# design.net
KiCad netlist of a schematic drawn in Altium Designer
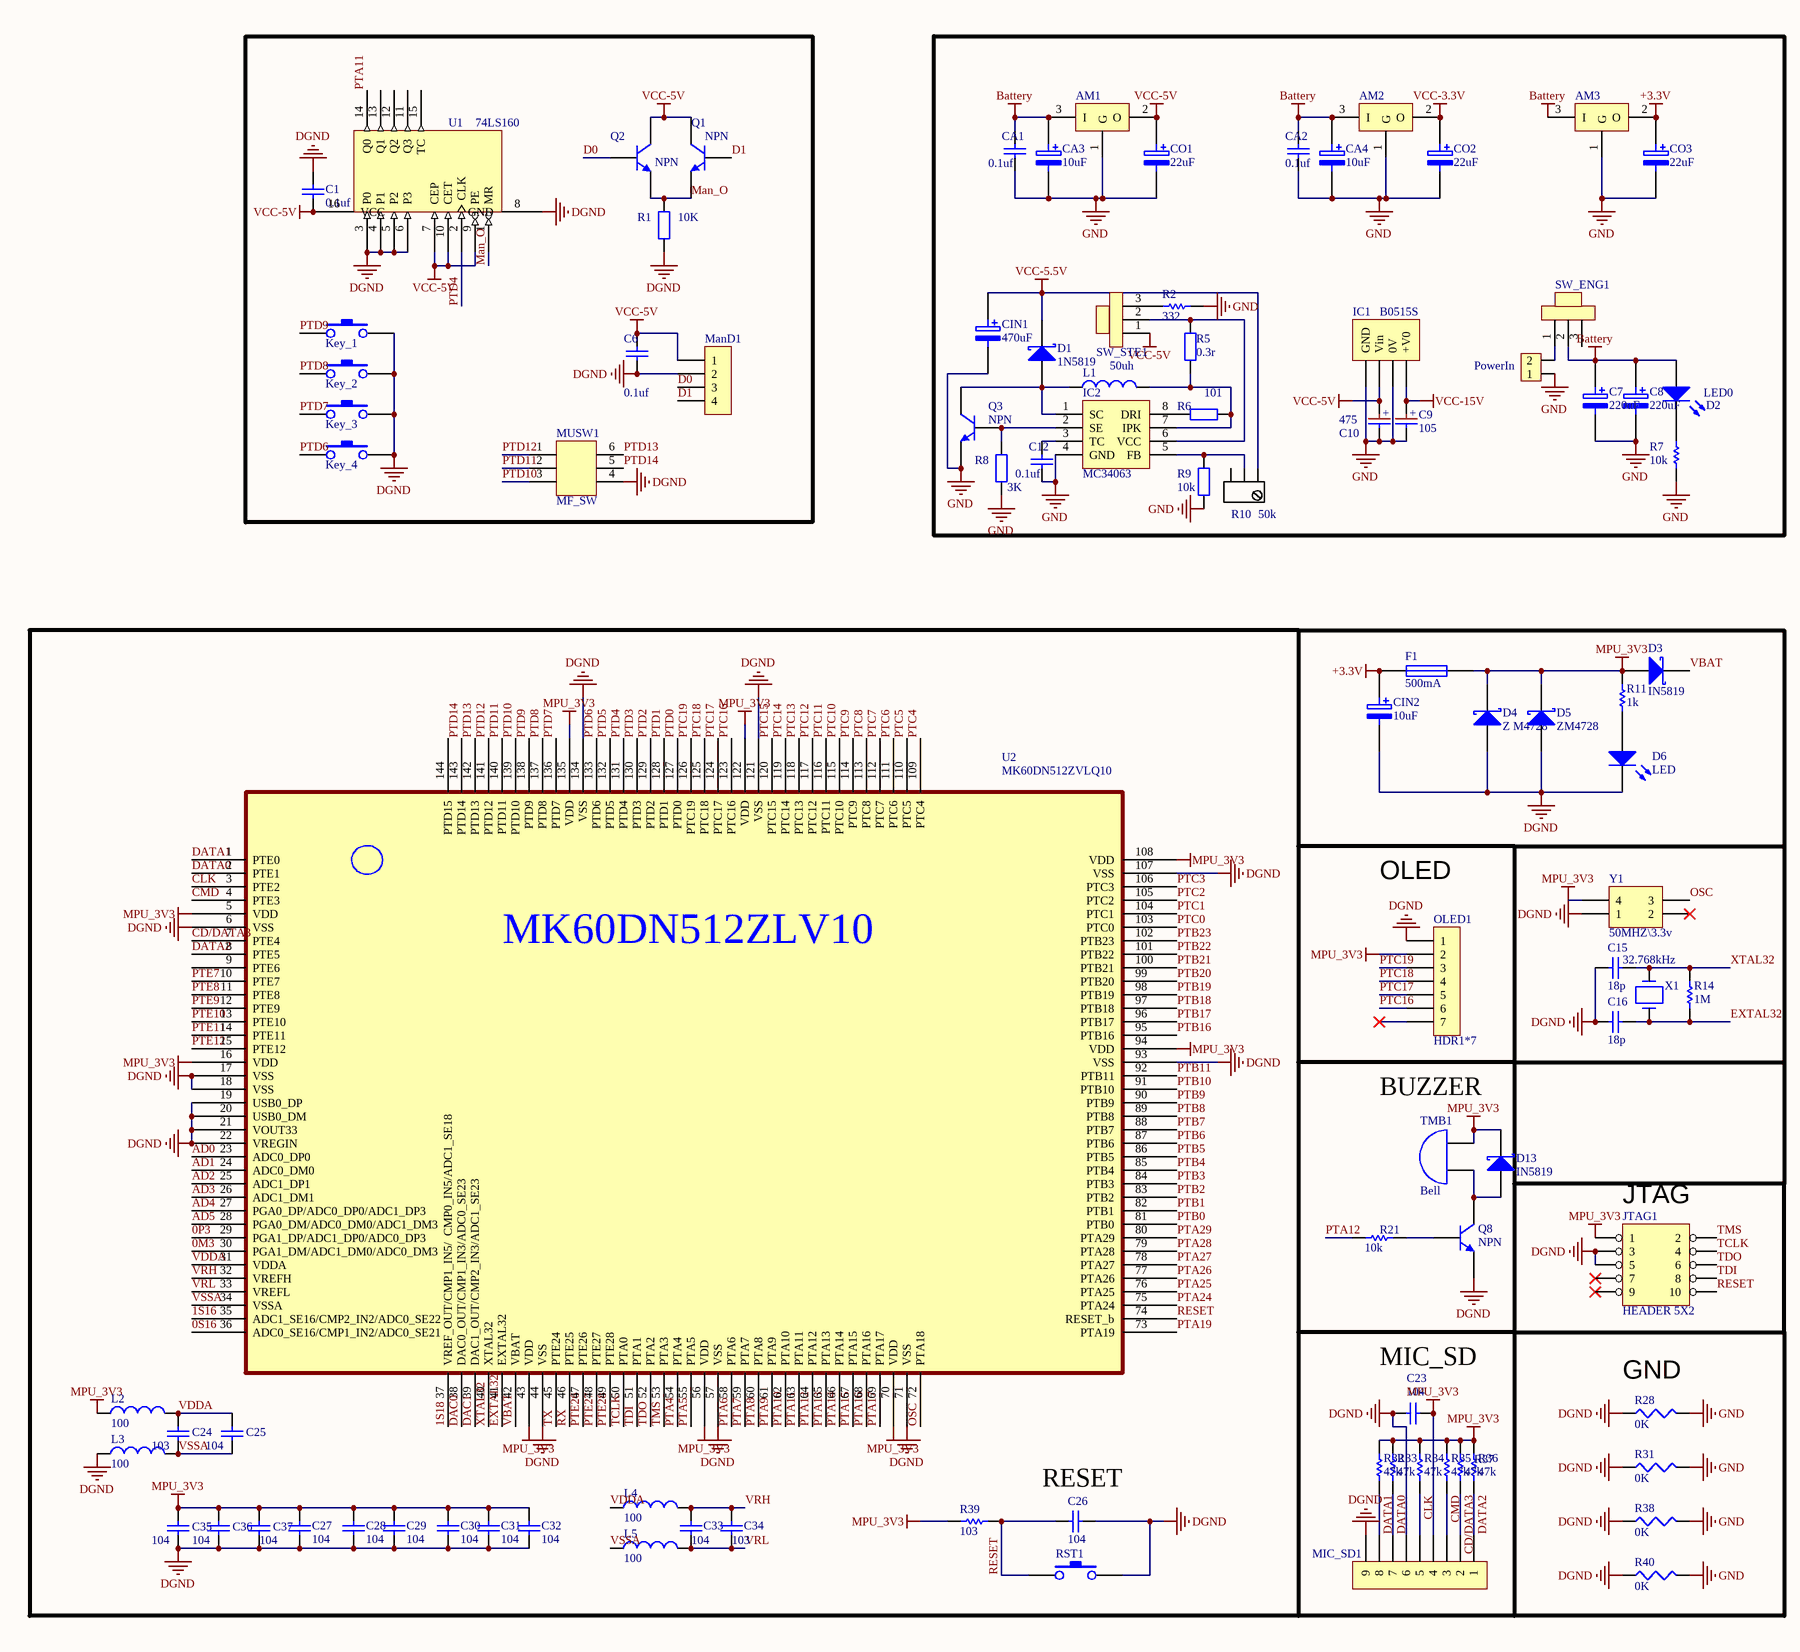
[diagram p0: 夏友.SchDoc, left]
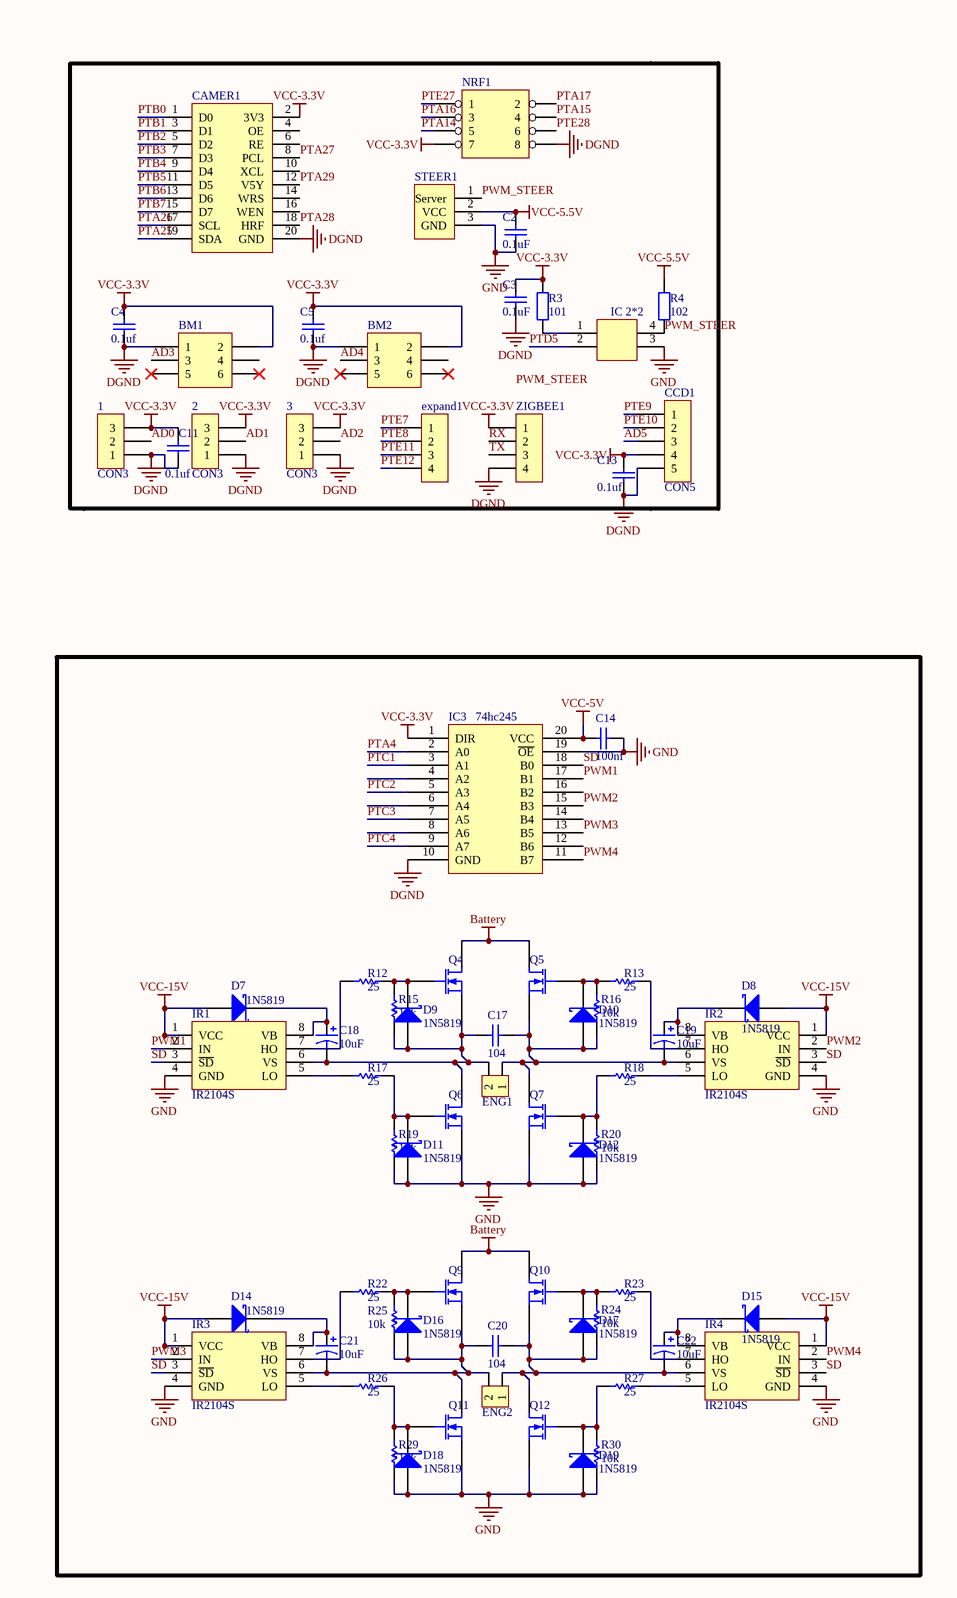
[diagram p1: 夏友.SchDoc, right]

(export (version "E")
  (design (tool "Eeschema 10.0.6"))
  (components
    (comp (ref "*1") (value "IC 2*2") (footprint "PC817") (libsource (lib "component") (part "IC 2*2")))
    (comp (ref "1")
      (value "CON3")
      (footprint "HDR1*3")
      (description "Connector")
      (libsource (lib "Miscellaneous Devices") (part "CON3"))
    )
    (comp (ref "2")
      (value "CON3")
      (footprint "HDR1*3")
      (description "Connector")
      (libsource (lib "Miscellaneous Devices") (part "CON3"))
    )
    (comp (ref "3")
      (value "CON3")
      (footprint "HDR1*3")
      (description "Connector")
      (libsource (lib "Miscellaneous Devices") (part "CON3"))
    )
    (comp (ref "AM1") (value "AMS1117") (footprint "SOT223") (libsource (lib "component") (part "AMS1117")))
    (comp (ref "AM2") (value "AMS1117") (footprint "SOT223") (libsource (lib "component") (part "AMS1117")))
    (comp (ref "AM3") (value "AMS1117") (footprint "SOT223") (libsource (lib "component") (part "AMS1117")))
    (comp (ref "BM1")
      (value "编码器左")
      (footprint "HDR2*3")
      (description "Header, 3-Pin, Dual row")
      (fields (field (name "PUBLISHER") "Altium Limited"))
      (libsource (lib "Miscellaneous Connectors") (part "Header 3X2"))
    )
    (comp (ref "BM2")
      (value "编码器左")
      (footprint "HDR2*3")
      (description "Header, 3-Pin, Dual row")
      (fields (field (name "PUBLISHER") "Altium Limited"))
      (libsource (lib "Miscellaneous Connectors") (part "Header 3X2"))
    )
    (comp (ref "C1")
      (value "0.1uf")
      (footprint "0603")
      (description "Capacitor (Semiconductor SIM Model)")
      (fields (field (name "Comment") "Cap Semi") (field (name "PUBLISHER") "Altium Limited"))
      (libsource (lib "Smartcar_Sheet") (part "Cap Semi_1"))
    )
    (comp (ref "C2")
      (value "0.1uF")
      (footprint "0603")
      (description "Capacitor")
      (fields (field (name "Comment") "Cap") (field (name "PUBLISHER") "Altium Limited"))
      (libsource (lib "省赛") (part "Cap"))
    )
    (comp (ref "C3")
      (value "0.1uF")
      (footprint "0603")
      (description "Capacitor")
      (fields (field (name "Comment") "Cap") (field (name "PUBLISHER") "Altium Limited"))
      (libsource (lib "省赛") (part "Cap"))
    )
    (comp (ref "C4")
      (value "0.1uf")
      (footprint "0603")
      (description "Capacitor (Semiconductor SIM Model)")
      (fields (field (name "Comment") "Cap Semi") (field (name "PUBLISHER") "Altium Limited"))
      (libsource (lib "Smartcar_Sheet") (part "Cap Semi_1"))
    )
    (comp (ref "C5")
      (value "0.1uf")
      (footprint "0603")
      (description "Capacitor (Semiconductor SIM Model)")
      (fields (field (name "Comment") "Cap Semi") (field (name "PUBLISHER") "Altium Limited"))
      (libsource (lib "Smartcar_Sheet") (part "Cap Semi_1"))
    )
    (comp (ref "C6")
      (value "0.1uf")
      (footprint "0603")
      (description "Capacitor (Semiconductor SIM Model)")
      (fields (field (name "Comment") "Cap Semi") (field (name "PUBLISHER") "Altium Limited"))
      (libsource (lib "Smartcar_Sheet") (part "Cap Semi_1"))
    )
    (comp (ref "C7")
      (value "220uF")
      (footprint "CAPMP7344X43N")
      (description "Electrolytic Capacitor")
      (libsource (lib "FS44B0") (part "ELECTRO2"))
    )
    (comp (ref "C8")
      (value "220uF")
      (footprint "CAPMP7344X43N")
      (description "Electrolytic Capacitor")
      (libsource (lib "FS44B0") (part "ELECTRO2"))
    )
    (comp (ref "C9")
      (value "105")
      (footprint "0805")
      (description "电容器")
      (libsource (lib "Smartcar_Sheet") (part "Cap--0805"))
    )
    (comp (ref "C10")
      (value "475")
      (footprint "0805")
      (description "电容器")
      (libsource (lib "Smartcar_Sheet") (part "Cap--0805"))
    )
    (comp (ref "C11")
      (value "0.1uf")
      (footprint "0603")
      (description "Capacitor (Semiconductor SIM Model)")
      (fields (field (name "Comment") "Cap Semi") (field (name "PUBLISHER") "Altium Limited"))
      (libsource (lib "Smartcar_Sheet") (part "Cap Semi_1"))
    )
    (comp (ref "C12")
      (value "0.1uf")
      (footprint "0603")
      (description "Capacitor (Semiconductor SIM Model)")
      (fields (field (name "Comment") "Cap Semi") (field (name "PUBLISHER") "Altium Limited"))
      (libsource (lib "Smartcar_Sheet") (part "Cap Semi_1"))
    )
    (comp (ref "C13")
      (value "0.1uf")
      (footprint "0603")
      (description "Capacitor (Semiconductor SIM Model)")
      (fields (field (name "Comment") "Cap Semi") (field (name "PUBLISHER") "Altium Limited"))
      (libsource (lib "Smartcar_Sheet") (part "Cap Semi_1"))
    )
    (comp (ref "C14")
      (value "100nf")
      (footprint "0603")
      (description "Capacitor (Semiconductor SIM Model)")
      (fields (field (name "Comment") "Cap Semi") (field (name "PUBLISHER") "Altium Limited"))
      (libsource (lib "Smartcar_Sheet") (part "Cap Semi_1"))
    )
    (comp (ref "C15")
      (value "18p")
      (footprint "0603")
      (description "Capacitor (Semiconductor SIM Model)")
      (fields (field (name "Comment") "Cap Semi") (field (name "PUBLISHER") "Altium Limited"))
      (libsource (lib "Smartcar_Sheet") (part "Cap Semi_1"))
    )
    (comp (ref "C16")
      (value "18p")
      (footprint "0603")
      (description "Capacitor (Semiconductor SIM Model)")
      (fields (field (name "Comment") "Cap Semi") (field (name "PUBLISHER") "Altium Limited"))
      (libsource (lib "Smartcar_Sheet") (part "Cap Semi_1"))
    )
    (comp (ref "C17")
      (value "104")
      (footprint "0603")
      (description "Capacitor (Semiconductor SIM Model)")
      (fields (field (name "Comment") "Cap Semi") (field (name "PUBLISHER") "Altium Limited"))
      (libsource (lib "Smartcar_Sheet") (part "Cap Semi_1"))
    )
    (comp (ref "C18")
      (value "10uF")
      (footprint "C1206")
      (description "Polarized Capacitor (Radial)")
      (fields (field (name "Comment") "1uF") (field (name "PUBLISHER") "Altium Limited"))
      (libsource (lib "Miscellaneous Devices") (part "Cap Pol1"))
    )
    (comp (ref "C19")
      (value "10uF")
      (footprint "C1206")
      (description "Polarized Capacitor (Radial)")
      (fields (field (name "Comment") "1uF") (field (name "PUBLISHER") "Altium Limited"))
      (libsource (lib "Miscellaneous Devices") (part "Cap Pol1"))
    )
    (comp (ref "C20")
      (value "104")
      (footprint "0603")
      (description "Capacitor (Semiconductor SIM Model)")
      (fields (field (name "Comment") "Cap Semi") (field (name "PUBLISHER") "Altium Limited"))
      (libsource (lib "Smartcar_Sheet") (part "Cap Semi_1"))
    )
    (comp (ref "C21")
      (value "10uF")
      (footprint "C1206")
      (description "Polarized Capacitor (Radial)")
      (fields (field (name "Comment") "1uF") (field (name "PUBLISHER") "Altium Limited"))
      (libsource (lib "Miscellaneous Devices") (part "Cap Pol1"))
    )
    (comp (ref "C22")
      (value "10uF")
      (footprint "C1206")
      (description "Polarized Capacitor (Radial)")
      (fields (field (name "Comment") "1uF") (field (name "PUBLISHER") "Altium Limited"))
      (libsource (lib "Miscellaneous Devices") (part "Cap Pol1"))
    )
    (comp (ref "C23")
      (value "104")
      (footprint "0603")
      (description "Capacitor (Semiconductor SIM Model)")
      (fields (field (name "Comment") "Cap Semi") (field (name "PUBLISHER") "Altium Limited"))
      (libsource (lib "Smartcar_Sheet") (part "Cap Semi_1"))
    )
    (comp (ref "C24")
      (value "103")
      (footprint "0603")
      (description "Capacitor (Semiconductor SIM Model)")
      (fields (field (name "Comment") "Cap Semi") (field (name "PUBLISHER") "Altium Limited"))
      (libsource (lib "Smartcar_Sheet") (part "Cap Semi_1"))
    )
    (comp (ref "C25")
      (value "104")
      (footprint "0603")
      (description "Capacitor (Semiconductor SIM Model)")
      (fields (field (name "Comment") "Cap Semi") (field (name "PUBLISHER") "Altium Limited"))
      (libsource (lib "Smartcar_Sheet") (part "Cap Semi_1"))
    )
    (comp (ref "C26")
      (value "104")
      (footprint "0603")
      (description "Capacitor (Semiconductor SIM Model)")
      (fields (field (name "Comment") "Cap Semi") (field (name "PUBLISHER") "Altium Limited"))
      (libsource (lib "Smartcar_Sheet") (part "Cap Semi_1"))
    )
    (comp (ref "C27")
      (value "104")
      (footprint "0603")
      (description "Capacitor (Semiconductor SIM Model)")
      (fields (field (name "Comment") "Cap Semi") (field (name "PUBLISHER") "Altium Limited"))
      (libsource (lib "Smartcar_Sheet") (part "Cap Semi_1"))
    )
    (comp (ref "C28")
      (value "104")
      (footprint "0603")
      (description "Capacitor (Semiconductor SIM Model)")
      (fields (field (name "Comment") "Cap Semi") (field (name "PUBLISHER") "Altium Limited"))
      (libsource (lib "Smartcar_Sheet") (part "Cap Semi_1"))
    )
    (comp (ref "C29")
      (value "104")
      (footprint "0603")
      (description "Capacitor (Semiconductor SIM Model)")
      (fields (field (name "Comment") "Cap Semi") (field (name "PUBLISHER") "Altium Limited"))
      (libsource (lib "Smartcar_Sheet") (part "Cap Semi_1"))
    )
    (comp (ref "C30")
      (value "104")
      (footprint "0603")
      (description "Capacitor (Semiconductor SIM Model)")
      (fields (field (name "Comment") "Cap Semi") (field (name "PUBLISHER") "Altium Limited"))
      (libsource (lib "Smartcar_Sheet") (part "Cap Semi_1"))
    )
    (comp (ref "C31")
      (value "104")
      (footprint "0603")
      (description "Capacitor (Semiconductor SIM Model)")
      (fields (field (name "Comment") "Cap Semi") (field (name "PUBLISHER") "Altium Limited"))
      (libsource (lib "Smartcar_Sheet") (part "Cap Semi_1"))
    )
    (comp (ref "C32")
      (value "104")
      (footprint "0603")
      (description "Capacitor (Semiconductor SIM Model)")
      (fields (field (name "Comment") "Cap Semi") (field (name "PUBLISHER") "Altium Limited"))
      (libsource (lib "Smartcar_Sheet") (part "Cap Semi_1"))
    )
    (comp (ref "C33")
      (value "104")
      (footprint "0603")
      (description "Capacitor (Semiconductor SIM Model)")
      (fields (field (name "Comment") "Cap Semi") (field (name "PUBLISHER") "Altium Limited"))
      (libsource (lib "Smartcar_Sheet") (part "Cap Semi_1"))
    )
    (comp (ref "C34")
      (value "103")
      (footprint "0603")
      (description "Capacitor (Semiconductor SIM Model)")
      (fields (field (name "Comment") "Cap Semi") (field (name "PUBLISHER") "Altium Limited"))
      (libsource (lib "Smartcar_Sheet") (part "Cap Semi_1"))
    )
    (comp (ref "C35")
      (value "104")
      (footprint "0603")
      (description "Capacitor (Semiconductor SIM Model)")
      (fields (field (name "Comment") "Cap Semi") (field (name "PUBLISHER") "Altium Limited"))
      (libsource (lib "Smartcar_Sheet") (part "Cap Semi_1"))
    )
    (comp (ref "C36")
      (value "104")
      (footprint "0603")
      (description "Capacitor (Semiconductor SIM Model)")
      (fields (field (name "Comment") "Cap Semi") (field (name "PUBLISHER") "Altium Limited"))
      (libsource (lib "Smartcar_Sheet") (part "Cap Semi_1"))
    )
    (comp (ref "C37")
      (value "104")
      (footprint "0603")
      (description "Capacitor (Semiconductor SIM Model)")
      (fields (field (name "Comment") "Cap Semi") (field (name "PUBLISHER") "Altium Limited"))
      (libsource (lib "Smartcar_Sheet") (part "Cap Semi_1"))
    )
    (comp (ref "CA1")
      (value "0.1uf")
      (footprint "0603")
      (description "Capacitor (Semiconductor SIM Model)")
      (fields (field (name "Comment") "Cap Semi") (field (name "PUBLISHER") "Altium Limited"))
      (libsource (lib "Smartcar_Sheet") (part "Cap Semi_1"))
    )
    (comp (ref "CA2")
      (value "0.1uf")
      (footprint "0603")
      (description "Capacitor (Semiconductor SIM Model)")
      (fields (field (name "Comment") "Cap Semi") (field (name "PUBLISHER") "Altium Limited"))
      (libsource (lib "Smartcar_Sheet") (part "Cap Semi_1"))
    )
    (comp (ref "CA3")
      (value "10uF")
      (footprint "C1206")
      (description "Electrolytic Capacitor")
      (libsource (lib "FS44B0") (part "ELECTRO2"))
    )
    (comp (ref "CA4")
      (value "10uF")
      (footprint "C1206")
      (description "Electrolytic Capacitor")
      (libsource (lib "FS44B0") (part "ELECTRO2"))
    )
    (comp (ref "CAMER1")
      (value "CAMER")
      (footprint "HDR2*10-10*25")
      (libsource (lib "component") (part "CAMER"))
    )
    (comp (ref "CCD1")
      (value "CON5")
      (footprint "HDR1*5")
      (description "Connector")
      (libsource (lib "Miscellaneous Devices") (part "CON5"))
    )
    (comp (ref "CIN1")
      (value "470uF")
      (footprint "470uf-column")
      (description "Electrolytic Capacitor")
      (libsource (lib "FS44B0") (part "ELECTRO2"))
    )
    (comp (ref "CIN2")
      (value "10uF")
      (footprint "C1206")
      (description "Electrolytic Capacitor")
      (libsource (lib "FS44B0") (part "ELECTRO2"))
    )
    (comp (ref "CO1")
      (value "22uF")
      (footprint "C1206")
      (description "Electrolytic Capacitor")
      (libsource (lib "FS44B0") (part "ELECTRO2"))
    )
    (comp (ref "CO2")
      (value "22uF")
      (footprint "C1206")
      (description "Electrolytic Capacitor")
      (libsource (lib "FS44B0") (part "ELECTRO2"))
    )
    (comp (ref "CO3")
      (value "22uF")
      (footprint "C1206")
      (description "Electrolytic Capacitor")
      (libsource (lib "FS44B0") (part "ELECTRO2"))
    )
    (comp (ref "CON1")
      (value "PowerIn")
      (footprint "Battery")
      (description "Header, 2-Pin")
      (libsource (lib "") (part "Header 2_1"))
    )
    (comp (ref "D1")
      (value "1N5819")
      (footprint "SS14")
      (description "Schottky Rectifier")
      (fields (field (name "PUBLISHER") "Altium Limited"))
      (libsource (lib "Miscellaneous Devices") (part "Diode 11DQ03"))
    )
    (comp (ref "D2")
      (value "LED0")
      (footprint "0805")
      (description "Typical INFRARED GaAs LED")
      (fields (field (name "PUBLISHER") "Altium Limited"))
      (libsource (lib "Miscellaneous Devices") (part "LED0"))
    )
    (comp (ref "D3")
      (value "IN5819")
      (footprint "SS14")
      (description "Schottky Diode")
      (fields (field (name "PUBLISHER") "Altium Limited"))
      (libsource (lib "FS44B0") (part "D Schottky"))
    )
    (comp (ref "D4")
      (value "Z M4728")
      (footprint "LL41")
      (description "Schottky Diode")
      (fields (field (name "PUBLISHER") "Altium Limited"))
      (libsource (lib "FS44B0") (part "D Schottky"))
    )
    (comp (ref "D5")
      (value "ZM4728")
      (footprint "LL41")
      (description "Schottky Diode")
      (fields (field (name "PUBLISHER") "Altium Limited"))
      (libsource (lib "FS44B0") (part "D Schottky"))
    )
    (comp (ref "D6")
      (value "LED")
      (footprint "0805")
      (description "发光二极管")
      (libsource (lib "Smartcar_Sheet") (part "LED"))
    )
    (comp (ref "D7")
      (value "1N5819")
      (footprint "SS14")
      (description "Schottky Rectifier")
      (fields (field (name "PUBLISHER") "Altium Limited"))
      (libsource (lib "Miscellaneous Devices") (part "Diode 11DQ03"))
    )
    (comp (ref "D8")
      (value "1N5819")
      (footprint "SS14")
      (description "Schottky Rectifier")
      (fields (field (name "PUBLISHER") "Altium Limited"))
      (libsource (lib "Miscellaneous Devices") (part "Diode 11DQ03"))
    )
    (comp (ref "D9")
      (value "1N5819")
      (footprint "SS14")
      (description "Schottky Rectifier")
      (fields (field (name "PUBLISHER") "Altium Limited"))
      (libsource (lib "Miscellaneous Devices") (part "Diode 11DQ03"))
    )
    (comp (ref "D10")
      (value "1N5819")
      (footprint "SS14")
      (description "Schottky Rectifier")
      (fields (field (name "PUBLISHER") "Altium Limited"))
      (libsource (lib "Miscellaneous Devices") (part "Diode 11DQ03"))
    )
    (comp (ref "D11")
      (value "1N5819")
      (footprint "SS14")
      (description "Schottky Rectifier")
      (fields (field (name "PUBLISHER") "Altium Limited"))
      (libsource (lib "Miscellaneous Devices") (part "Diode 11DQ03"))
    )
    (comp (ref "D12")
      (value "1N5819")
      (footprint "SS14")
      (description "Schottky Rectifier")
      (fields (field (name "PUBLISHER") "Altium Limited"))
      (libsource (lib "Miscellaneous Devices") (part "Diode 11DQ03"))
    )
    (comp (ref "D13")
      (value "IN5819")
      (footprint "SS14")
      (description "Schottky Diode")
      (fields (field (name "PUBLISHER") "Altium Limited"))
      (libsource (lib "Miscellaneous Devices") (part "D Schottky"))
    )
    (comp (ref "D14")
      (value "1N5819")
      (footprint "SS14")
      (description "Schottky Rectifier")
      (fields (field (name "PUBLISHER") "Altium Limited"))
      (libsource (lib "Miscellaneous Devices") (part "Diode 11DQ03"))
    )
    (comp (ref "D15")
      (value "1N5819")
      (footprint "SS14")
      (description "Schottky Rectifier")
      (fields (field (name "PUBLISHER") "Altium Limited"))
      (libsource (lib "Miscellaneous Devices") (part "Diode 11DQ03"))
    )
    (comp (ref "D16")
      (value "1N5819")
      (footprint "SS14")
      (description "Schottky Rectifier")
      (fields (field (name "PUBLISHER") "Altium Limited"))
      (libsource (lib "Miscellaneous Devices") (part "Diode 11DQ03"))
    )
    (comp (ref "D17")
      (value "1N5819")
      (footprint "SS14")
      (description "Schottky Rectifier")
      (fields (field (name "PUBLISHER") "Altium Limited"))
      (libsource (lib "Miscellaneous Devices") (part "Diode 11DQ03"))
    )
    (comp (ref "D18")
      (value "1N5819")
      (footprint "SS14")
      (description "Schottky Rectifier")
      (fields (field (name "PUBLISHER") "Altium Limited"))
      (libsource (lib "Miscellaneous Devices") (part "Diode 11DQ03"))
    )
    (comp (ref "D19")
      (value "1N5819")
      (footprint "SS14")
      (description "Schottky Rectifier")
      (fields (field (name "PUBLISHER") "Altium Limited"))
      (libsource (lib "Miscellaneous Devices") (part "Diode 11DQ03"))
    )
    (comp (ref "ENG1")
      (value "PowerIn")
      (footprint "Dynamo")
      (description "Header, 2-Pin")
      (libsource (lib "MOS motor driving module ") (part "Header 2"))
    )
    (comp (ref "ENG2")
      (value "PowerIn")
      (footprint "Dynamo")
      (description "Header, 2-Pin")
      (libsource (lib "MOS motor driving module ") (part "Header 2"))
    )
    (comp (ref "expand1")
      (value "CON4")
      (footprint "HDR1*4")
      (description "Connector")
      (libsource (lib "Miscellaneous Devices") (part "CON4"))
    )
    (comp (ref "F1") (value "500mA") (footprint "1206") (libsource (lib "Smartcar_Sheet") (part "FUSE")))
    (comp (ref "IC1") (value "B0515S") (footprint "B0512S") (libsource (lib "DIY-???") (part "B0512S-1W")))
    (comp (ref "IC2") (value "MC34063") (footprint "SO-8") (libsource (lib "component") (part "MC34063")))
    (comp (ref "IC3")
      (value "74hc245")
      (footprint "74HC245D")
      (description "8位5伏转3.3伏电平转换芯片")
      (libsource (lib "MOS motor driving module ") (part "74lvc245"))
    )
    (comp (ref "IR1")
      (value "IR2104S")
      (footprint "SO-8")
      (description "HALF-BRIDGE DRIVER")
      (libsource (lib "智能小车原理图库") (part "IR2104S"))
    )
    (comp (ref "IR2")
      (value "IR2104S")
      (footprint "SO-8")
      (description "HALF-BRIDGE DRIVER")
      (libsource (lib "") (part "IR2104S_1"))
    )
    (comp (ref "IR3")
      (value "IR2104S")
      (footprint "SO-8")
      (description "HALF-BRIDGE DRIVER")
      (libsource (lib "智能小车原理图库") (part "IR2104S"))
    )
    (comp (ref "IR4")
      (value "IR2104S")
      (footprint "SO-8")
      (description "HALF-BRIDGE DRIVER")
      (libsource (lib "") (part "IR2104S_1"))
    )
    (comp (ref "JTAG1")
      (value "HEADER 5X2")
      (footprint "HDR2*5")
      (libsource (lib "Miscellaneous Devices") (part "HEADER 5X2"))
    )
    (comp (ref "Key_1") (value "按钮开关") (footprint "KEY-2") (libsource (lib "集成元件库") (part "按钮开关")))
    (comp (ref "Key_2") (value "按钮开关") (footprint "KEY-2") (libsource (lib "集成元件库") (part "按钮开关")))
    (comp (ref "Key_3") (value "按钮开关") (footprint "KEY-2") (libsource (lib "集成元件库") (part "按钮开关")))
    (comp (ref "Key_4") (value "按钮开关") (footprint "KEY-2") (libsource (lib "集成元件库") (part "按钮开关")))
    (comp (ref "L1")
      (value "50uh")
      (footprint "INDUCTOR 12*12*7")
      (description "Inductor")
      (fields (field (name "PUBLISHER") "Altium Limited"))
      (libsource (lib "Smartcar_Sheet") (part "Inductor"))
    )
    (comp (ref "L2")
      (value "100")
      (footprint "0805")
      (description "Inductor")
      (fields (field (name "PUBLISHER") "Altium Limited"))
      (libsource (lib "Smartcar_Sheet") (part "Inductor"))
    )
    (comp (ref "L3")
      (value "100")
      (footprint "0805")
      (description "Inductor")
      (fields (field (name "PUBLISHER") "Altium Limited"))
      (libsource (lib "Smartcar_Sheet") (part "Inductor"))
    )
    (comp (ref "L4")
      (value "100")
      (footprint "0805")
      (description "Inductor")
      (fields (field (name "PUBLISHER") "Altium Limited"))
      (libsource (lib "Smartcar_Sheet") (part "Inductor"))
    )
    (comp (ref "L5")
      (value "100")
      (footprint "0805")
      (description "Inductor")
      (fields (field (name "PUBLISHER") "Altium Limited"))
      (libsource (lib "Smartcar_Sheet") (part "Inductor"))
    )
    (comp (ref "ManD1") (value "HDR1*4") (footprint "HDR1*4") (libsource (lib "component") (part "HDR1*4")))
    (comp (ref "MIC_SD1")
      (value "ON9")
      (footprint "TF-2")
      (description "Connector")
      (libsource (lib "Miscellaneous Devices") (part "CON9"))
    )
    (comp (ref "MUSW1") (value "MF_SW") (footprint "MUL_SW") (libsource (lib "component") (part "MF_SW")))
    (comp (ref "NRF1")
      (value "HEADER 4X2")
      (footprint "HDR2*4")
      (libsource (lib "Miscellaneous Devices") (part "HEADER 4X2"))
    )
    (comp (ref "OLED1") (value "HDR1*7") (footprint "HDR1*7") (libsource (lib "component") (part "HDR1*7")))
    (comp (ref "Q1")
      (value "NPN")
      (footprint "SOT95P280X125-3N")
      (description "NPN Bipolar Transistor")
      (fields (field (name "PUBLISHER") "Altium Limited"))
      (libsource (lib "Miscellaneous Devices") (part "QNPN"))
    )
    (comp (ref "Q2")
      (value "NPN")
      (footprint "SOT95P280X125-3N")
      (description "NPN Bipolar Transistor")
      (fields (field (name "PUBLISHER") "Altium Limited"))
      (libsource (lib "Miscellaneous Devices") (part "QNPN"))
    )
    (comp (ref "Q3")
      (value "NPN")
      (footprint "SOT95P280X125-3N")
      (description "NPN Bipolar Transistor")
      (fields (field (name "PUBLISHER") "Altium Limited"))
      (libsource (lib "Miscellaneous Devices") (part "QNPN"))
    )
    (comp (ref "Q4")
      (value "MOSFET-N")
      (footprint "LR7843")
      (description "N-Channel MOSFET")
      (fields (field (name "PUBLISHER") "Altium Limited"))
      (libsource (lib "Miscellaneous Devices") (part "MOSFET-N"))
    )
    (comp (ref "Q5")
      (value "MOSFET-N")
      (footprint "LR7843")
      (description "N-Channel MOSFET")
      (fields (field (name "PUBLISHER") "Altium Limited"))
      (libsource (lib "Miscellaneous Devices") (part "MOSFET-N"))
    )
    (comp (ref "Q6")
      (value "MOSFET-N")
      (footprint "LR7843")
      (description "N-Channel MOSFET")
      (fields (field (name "PUBLISHER") "Altium Limited"))
      (libsource (lib "Miscellaneous Devices") (part "MOSFET-N"))
    )
    (comp (ref "Q7")
      (value "MOSFET-N")
      (footprint "LR7843")
      (description "N-Channel MOSFET")
      (fields (field (name "PUBLISHER") "Altium Limited"))
      (libsource (lib "Miscellaneous Devices") (part "MOSFET-N"))
    )
    (comp (ref "Q8")
      (value "NPN")
      (footprint "SOT95P280X125-3N")
      (description "NPN Bipolar Transistor")
      (fields (field (name "PUBLISHER") "Altium Limited"))
      (libsource (lib "Miscellaneous Devices") (part "QNPN"))
    )
    (comp (ref "Q9")
      (value "MOSFET-N")
      (footprint "LR7843")
      (description "N-Channel MOSFET")
      (fields (field (name "PUBLISHER") "Altium Limited"))
      (libsource (lib "Miscellaneous Devices") (part "MOSFET-N"))
    )
    (comp (ref "Q10")
      (value "MOSFET-N")
      (footprint "LR7843")
      (description "N-Channel MOSFET")
      (fields (field (name "PUBLISHER") "Altium Limited"))
      (libsource (lib "Miscellaneous Devices") (part "MOSFET-N"))
    )
    (comp (ref "Q11")
      (value "MOSFET-N")
      (footprint "LR7843")
      (description "N-Channel MOSFET")
      (fields (field (name "PUBLISHER") "Altium Limited"))
      (libsource (lib "Miscellaneous Devices") (part "MOSFET-N"))
    )
    (comp (ref "Q12")
      (value "MOSFET-N")
      (footprint "LR7843")
      (description "N-Channel MOSFET")
      (fields (field (name "PUBLISHER") "Altium Limited"))
      (libsource (lib "Miscellaneous Devices") (part "MOSFET-N"))
    )
    (comp (ref "R1")
      (value "10K")
      (footprint "0603")
      (description "Resistor")
      (fields (field (name "Comment") "Res2") (field (name "PUBLISHER") "Altium Limited"))
      (libsource (lib "Miscellaneous Devices") (part "Res2"))
    )
    (comp (ref "R2")
      (value "332")
      (footprint "0805")
      (description "电阻")
      (libsource (lib "Smartcar_Sheet") (part "Res"))
    )
    (comp (ref "R3")
      (value "101")
      (footprint "0603")
      (description "Resistor")
      (fields (field (name "Comment") "Res2") (field (name "PUBLISHER") "Altium Limited"))
      (libsource (lib "Miscellaneous Devices") (part "Res2"))
    )
    (comp (ref "R4")
      (value "102")
      (footprint "0603")
      (description "Resistor")
      (fields (field (name "Comment") "Res2") (field (name "PUBLISHER") "Altium Limited"))
      (libsource (lib "Miscellaneous Devices") (part "Res2"))
    )
    (comp (ref "R5")
      (value "0.3r")
      (footprint "0603")
      (description "Resistor")
      (fields (field (name "Comment") "Res2") (field (name "PUBLISHER") "Altium Limited"))
      (libsource (lib "Miscellaneous Devices") (part "Res2"))
    )
    (comp (ref "R6")
      (value "101")
      (footprint "0603")
      (description "Resistor")
      (fields (field (name "Comment") "Res2") (field (name "PUBLISHER") "Altium Limited"))
      (libsource (lib "") (part "Res2_1"))
    )
    (comp (ref "R7")
      (value "10k")
      (footprint "0805")
      (description "电阻")
      (libsource (lib "Smartcar_Sheet") (part "Res"))
    )
    (comp (ref "R8")
      (value "3K")
      (footprint "0603")
      (description "Resistor")
      (fields (field (name "Comment") "Res2") (field (name "PUBLISHER") "Altium Limited"))
      (libsource (lib "Miscellaneous Devices") (part "Res2"))
    )
    (comp (ref "R9")
      (value "10k")
      (footprint "0603")
      (description "Resistor")
      (fields (field (name "Comment") "Res2") (field (name "PUBLISHER") "Altium Limited"))
      (libsource (lib "") (part "Res2_2"))
    )
    (comp (ref "R10") (value "50k") (footprint "HDR1*3") (libsource (lib "单片机") (part "精密电位器")))
    (comp (ref "R11")
      (value "1k")
      (footprint "0805")
      (description "电阻")
      (libsource (lib "Smartcar_Sheet") (part "Res"))
    )
    (comp (ref "R12")
      (value "25")
      (footprint "0603")
      (description "Resistor")
      (fields (field (name "Comment") "Res1") (field (name "PUBLISHER") "Altium Limited"))
      (libsource (lib "Miscellaneous Devices") (part "Res1"))
    )
    (comp (ref "R13")
      (value "25")
      (footprint "0603")
      (description "Resistor")
      (fields (field (name "Comment") "Res1") (field (name "PUBLISHER") "Altium Limited"))
      (libsource (lib "Miscellaneous Devices") (part "Res1"))
    )
    (comp (ref "R14")
      (value "1M")
      (footprint "0603")
      (description "电阻")
      (libsource (lib "Smartcar_Sheet") (part "Res"))
    )
    (comp (ref "R15")
      (value "10k")
      (footprint "0805")
      (description "Resistor")
      (fields (field (name "Comment") "Res1") (field (name "PUBLISHER") "Altium Limited"))
      (libsource (lib "Miscellaneous Devices") (part "Res1"))
    )
    (comp (ref "R16")
      (value "10k")
      (footprint "0805")
      (description "Resistor")
      (fields (field (name "Comment") "Res1") (field (name "PUBLISHER") "Altium Limited"))
      (libsource (lib "Miscellaneous Devices") (part "Res1"))
    )
    (comp (ref "R17")
      (value "25")
      (footprint "0603")
      (description "Resistor")
      (fields (field (name "Comment") "Res1") (field (name "PUBLISHER") "Altium Limited"))
      (libsource (lib "Miscellaneous Devices") (part "Res1"))
    )
    (comp (ref "R18")
      (value "25")
      (footprint "0603")
      (description "Resistor")
      (fields (field (name "Comment") "Res1") (field (name "PUBLISHER") "Altium Limited"))
      (libsource (lib "Miscellaneous Devices") (part "Res1"))
    )
    (comp (ref "R19")
      (value "10k")
      (footprint "0805")
      (description "Resistor")
      (fields (field (name "Comment") "Res1") (field (name "PUBLISHER") "Altium Limited"))
      (libsource (lib "Miscellaneous Devices") (part "Res1"))
    )
    (comp (ref "R20")
      (value "10k")
      (footprint "0805")
      (description "Resistor")
      (fields (field (name "Comment") "Res1") (field (name "PUBLISHER") "Altium Limited"))
      (libsource (lib "Miscellaneous Devices") (part "Res1"))
    )
    (comp (ref "R21")
      (value "10k")
      (footprint "0603")
      (description "电阻")
      (libsource (lib "Smartcar_Sheet") (part "Res"))
    )
    (comp (ref "R22")
      (value "25")
      (footprint "0603")
      (description "Resistor")
      (fields (field (name "Comment") "Res1") (field (name "PUBLISHER") "Altium Limited"))
      (libsource (lib "Miscellaneous Devices") (part "Res1"))
    )
    (comp (ref "R23")
      (value "25")
      (footprint "0603")
      (description "Resistor")
      (fields (field (name "Comment") "Res1") (field (name "PUBLISHER") "Altium Limited"))
      (libsource (lib "Miscellaneous Devices") (part "Res1"))
    )
    (comp (ref "R24")
      (value "10k")
      (footprint "0805")
      (description "Resistor")
      (fields (field (name "Comment") "Res1") (field (name "PUBLISHER") "Altium Limited"))
      (libsource (lib "Miscellaneous Devices") (part "Res1"))
    )
    (comp (ref "R25")
      (value "10k")
      (footprint "0805")
      (description "Resistor")
      (fields (field (name "Comment") "Res1") (field (name "PUBLISHER") "Altium Limited"))
      (libsource (lib "Miscellaneous Devices") (part "Res1"))
    )
    (comp (ref "R26")
      (value "25")
      (footprint "0603")
      (description "Resistor")
      (fields (field (name "Comment") "Res1") (field (name "PUBLISHER") "Altium Limited"))
      (libsource (lib "Miscellaneous Devices") (part "Res1"))
    )
    (comp (ref "R27")
      (value "25")
      (footprint "0603")
      (description "Resistor")
      (fields (field (name "Comment") "Res1") (field (name "PUBLISHER") "Altium Limited"))
      (libsource (lib "Miscellaneous Devices") (part "Res1"))
    )
    (comp (ref "R28")
      (value "0K")
      (footprint "0805")
      (description "Resistor")
      (fields (field (name "Comment") "Res3") (field (name "PUBLISHER") "Altium Limited"))
      (libsource (lib "Miscellaneous Devices") (part "Res3"))
    )
    (comp (ref "R29")
      (value "10k")
      (footprint "0805")
      (description "Resistor")
      (fields (field (name "Comment") "Res1") (field (name "PUBLISHER") "Altium Limited"))
      (libsource (lib "Miscellaneous Devices") (part "Res1"))
    )
    (comp (ref "R30")
      (value "10k")
      (footprint "0805")
      (description "Resistor")
      (fields (field (name "Comment") "Res1") (field (name "PUBLISHER") "Altium Limited"))
      (libsource (lib "Miscellaneous Devices") (part "Res1"))
    )
    (comp (ref "R31")
      (value "0K")
      (footprint "0805")
      (description "Resistor")
      (fields (field (name "Comment") "Res3") (field (name "PUBLISHER") "Altium Limited"))
      (libsource (lib "Miscellaneous Devices") (part "Res3"))
    )
    (comp (ref "R32")
      (value "47k")
      (footprint "0603")
      (description "电阻")
      (libsource (lib "Smartcar_Sheet") (part "Res"))
    )
    (comp (ref "R33")
      (value "47k")
      (footprint "0603")
      (description "电阻")
      (libsource (lib "Smartcar_Sheet") (part "Res"))
    )
    (comp (ref "R34")
      (value "47k")
      (footprint "0603")
      (description "电阻")
      (libsource (lib "Smartcar_Sheet") (part "Res"))
    )
    (comp (ref "R35")
      (value "47k")
      (footprint "0603")
      (description "电阻")
      (libsource (lib "Smartcar_Sheet") (part "Res"))
    )
    (comp (ref "R36")
      (value "47k")
      (footprint "0603")
      (description "电阻")
      (libsource (lib "Smartcar_Sheet") (part "Res"))
    )
    (comp (ref "R37")
      (value "47k")
      (footprint "0603")
      (description "电阻")
      (libsource (lib "Smartcar_Sheet") (part "Res"))
    )
    (comp (ref "R38")
      (value "0K")
      (footprint "0805")
      (description "Resistor")
      (fields (field (name "Comment") "Res3") (field (name "PUBLISHER") "Altium Limited"))
      (libsource (lib "Miscellaneous Devices") (part "Res3"))
    )
    (comp (ref "R39")
      (value "103")
      (footprint "0805")
      (description "电阻")
      (libsource (lib "Smartcar_Sheet") (part "Res"))
    )
    (comp (ref "R40")
      (value "0K")
      (footprint "0805")
      (description "Resistor")
      (fields (field (name "Comment") "Res3") (field (name "PUBLISHER") "Altium Limited"))
      (libsource (lib "Miscellaneous Devices") (part "Res3"))
    )
    (comp (ref "RST1") (value "按钮开关") (footprint "KEY-2") (libsource (lib "集成元件库") (part "按钮开关")))
    (comp (ref "STEER1")
      (value "Header_Server")
      (footprint "HDR1X3")
      (libsource (lib "智能小车原理图库") (part "Header_Server"))
    )
    (comp (ref "SW_ENG1")
      (value "SWITCH_B")
      (footprint "ss12")
      (libsource (lib "component") (part "SWITCH_B"))
    )
    (comp (ref "SW_STE1") (value "SWITCH_B") (footprint "ss12") (libsource (lib "") (part "SWITCH_B_1")))
    (comp (ref "TMB1")
      (value "Bell")
      (footprint "DIP_buzzer")
      (description "Electrical Bell")
      (fields (field (name "PUBLISHER") "Altium Limited"))
      (libsource (lib "Miscellaneous Devices") (part "Bell"))
    )
    (comp (ref "U1") (value "74LS160") (footprint "SOIC-16") (libsource (lib "TTL74??IC") (part "74LS160")))
    (comp (ref "U2")
      (value "MK60DN512ZVLQ10")
      (footprint "MK60DN512ZVLQ10")
      (description "K60")
      (libsource (lib "Smartcar_Sheet") (part "MK60DN512ZVLQ10"))
    )
    (comp (ref "X1")
      (value "32.768kHz")
      (footprint "XT 32768")
      (libsource (lib "FS44B0_CORE") (part "CRYSTAL_1"))
    )
    (comp (ref "Y1")
      (value "50MH~{Z}3.3v")
      (footprint "有源晶振5*3.2")
      (libsource (lib "component") (part "50MHZ{backslash}3.3v"))
    )
    (comp (ref "ZIGBEE1")
      (value "CON4")
      (footprint "HDR1*4")
      (description "Connector")
      (libsource (lib "Miscellaneous Devices") (part "CON4"))
    )
  )
  (nets
    (net (code "1") (name "+3.3V") (class "Default")
      (node (ref "AM3") (pin "2") (pinfunction "O_2") (pintype "passive"))
      (node (ref "CIN2") (pin "1") (pinfunction "1_1") (pintype "passive"))
      (node (ref "CO3") (pin "1") (pinfunction "1_1") (pintype "passive"))
      (node (ref "F1") (pin "1") (pinfunction "1_1") (pintype "passive"))
    )
    (net (code "2") (name "/0M3") (class "Default")
      (node (ref "U2") (pin "30") (pinfunction "PGA1_DM/ADC1_DM0/ADC0_DM3_30") (pintype "passive"))
    )
    (net (code "3") (name "/0P3") (class "Default")
      (node (ref "U2") (pin "29") (pinfunction "PGA1_DP/ADC1_DP0/ADC0_DP3_29") (pintype "passive"))
    )
    (net (code "4") (name "/0S16") (class "Default")
      (node (ref "U2") (pin "36") (pinfunction "ADC0_SE16/CMP1_IN2/ADC0_SE21_36") (pintype "passive"))
    )
    (net (code "5") (name "/1S16") (class "Default")
      (node (ref "U2") (pin "35") (pinfunction "ADC1_SE16/CMP2_IN2/ADC0_SE22_35") (pintype "passive"))
    )
    (net (code "6") (name "/1S18") (class "Default")
      (node (ref "U2") (pin "37") (pinfunction "VREF_OUT/CMP1_IN5/__CMP0_IN5/ADC1_SE18_37") (pintype "passive"))
    )
    (net (code "7") (name "/AD0") (class "Default")
      (node (ref "1") (pin "2") (pinfunction "2_2") (pintype "passive"))
      (node (ref "U2") (pin "23") (pinfunction "ADC0_DP0_23") (pintype "passive"))
    )
    (net (code "8") (name "/AD1") (class "Default")
      (node (ref "2") (pin "2") (pinfunction "2_2") (pintype "passive"))
      (node (ref "U2") (pin "24") (pinfunction "ADC0_DM0_24") (pintype "passive"))
    )
    (net (code "9") (name "/AD2") (class "Default")
      (node (ref "3") (pin "2") (pinfunction "2_2") (pintype "passive"))
      (node (ref "U2") (pin "25") (pinfunction "ADC1_DP1_25") (pintype "passive"))
    )
    (net (code "10") (name "/AD3") (class "Default")
      (node (ref "BM1") (pin "3") (pinfunction "3_3") (pintype "passive"))
      (node (ref "U2") (pin "26") (pinfunction "ADC1_DM1_26") (pintype "passive"))
    )
    (net (code "11") (name "/AD4") (class "Default")
      (node (ref "BM2") (pin "3") (pinfunction "3_3") (pintype "passive"))
      (node (ref "U2") (pin "27") (pinfunction "PGA0_DP/ADC0_DP0/ADC1_DP3_27") (pintype "passive"))
    )
    (net (code "12") (name "/AD5") (class "Default")
      (node (ref "CCD1") (pin "3") (pinfunction "3_3") (pintype "passive"))
      (node (ref "U2") (pin "28") (pinfunction "PGA0_DM/ADC0_DM0/ADC1_DM3_28") (pintype "passive"))
    )
    (net (code "13") (name "/CD{slash}DATA3") (class "Default")
      (node (ref "MIC_SD1") (pin "2") (pinfunction "2_2") (pintype "passive"))
      (node (ref "R37") (pin "2") (pinfunction "2_2") (pintype "passive"))
      (node (ref "U2") (pin "7") (pinfunction "PTE4_7") (pintype "passive"))
    )
    (net (code "14") (name "/CLK") (class "Default")
      (node (ref "MIC_SD1") (pin "5") (pinfunction "5_5") (pintype "passive"))
      (node (ref "R34") (pin "2") (pinfunction "2_2") (pintype "passive"))
      (node (ref "U2") (pin "3") (pinfunction "PTE2_3") (pintype "passive"))
    )
    (net (code "15") (name "/CMD") (class "Default")
      (node (ref "MIC_SD1") (pin "3") (pinfunction "3_3") (pintype "passive"))
      (node (ref "R35") (pin "2") (pinfunction "2_2") (pintype "passive"))
      (node (ref "U2") (pin "4") (pinfunction "PTE3_4") (pintype "passive"))
    )
    (net (code "16") (name "/D0") (class "Default")
      (node (ref "ManD1") (pin "3") (pinfunction "3_3") (pintype "passive"))
      (node (ref "Q2") (pin "2") (pinfunction "B_2") (pintype "passive"))
    )
    (net (code "17") (name "/D1") (class "Default")
      (node (ref "ManD1") (pin "4") (pinfunction "4_4") (pintype "passive"))
      (node (ref "Q1") (pin "2") (pinfunction "B_2") (pintype "passive"))
    )
    (net (code "18") (name "/DAC0") (class "Default")
      (node (ref "U2") (pin "38") (pinfunction "DAC0_OUT/CMP1_IN3/ADC0_SE23_38") (pintype "passive"))
    )
    (net (code "19") (name "/DAC1") (class "Default")
      (node (ref "U2") (pin "39") (pinfunction "DAC1_OUT/CMP2_IN3/ADC1_SE23_39") (pintype "passive"))
    )
    (net (code "20") (name "/DATA0") (class "Default")
      (node (ref "MIC_SD1") (pin "7") (pinfunction "7_7") (pintype "passive"))
      (node (ref "R33") (pin "2") (pinfunction "2_2") (pintype "passive"))
      (node (ref "U2") (pin "2") (pinfunction "PTE1_2") (pintype "passive"))
    )
    (net (code "21") (name "/DATA1") (class "Default")
      (node (ref "MIC_SD1") (pin "8") (pinfunction "8_8") (pintype "passive"))
      (node (ref "R32") (pin "2") (pinfunction "2_2") (pintype "passive"))
      (node (ref "U2") (pin "1") (pinfunction "PTE0_1") (pintype "passive"))
    )
    (net (code "22") (name "/DATA2") (class "Default")
      (node (ref "MIC_SD1") (pin "1") (pinfunction "1_1") (pintype "passive"))
      (node (ref "R36") (pin "2") (pinfunction "2_2") (pintype "passive"))
      (node (ref "U2") (pin "8") (pinfunction "PTE5_8") (pintype "passive"))
    )
    (net (code "23") (name "/EXTAL32") (class "Default")
      (node (ref "C16") (pin "1") (pinfunction "1_1") (pintype "passive"))
      (node (ref "R14") (pin "2") (pinfunction "2_2") (pintype "passive"))
      (node (ref "U2") (pin "41") (pinfunction "EXTAL32_41") (pintype "passive"))
      (node (ref "X1") (pin "2") (pinfunction "2_2") (pintype "passive"))
    )
    (net (code "24") (name "/Man_O") (class "Default")
      (node (ref "Q1") (pin "3") (pinfunction "E_3") (pintype "passive"))
      (node (ref "Q2") (pin "3") (pinfunction "E_3") (pintype "passive"))
      (node (ref "R1") (pin "2") (pinfunction "2_2") (pintype "passive"))
      (node (ref "U1") (pin "1") (pinfunction "MR_1") (pintype "input"))
    )
    (net (code "25") (name "/OSC") (class "Default")
      (node (ref "U2") (pin "72") (pinfunction "PTA18_72") (pintype "passive"))
      (node (ref "Y1") (pin "3") (pinfunction "3_3") (pintype "passive"))
    )
    (net (code "26") (name "/PTA4") (class "Default")
      (node (ref "IC3") (pin "2") (pinfunction "A0_2") (pintype "passive"))
      (node (ref "U2") (pin "54") (pinfunction "PTA4_54") (pintype "passive"))
    )
    (net (code "27") (name "/PTA5") (class "Default")
      (node (ref "U2") (pin "55") (pinfunction "PTA5_55") (pintype "passive"))
    )
    (net (code "28") (name "/PTA6") (class "Default")
      (node (ref "U2") (pin "58") (pinfunction "PTA6_58") (pintype "passive"))
    )
    (net (code "29") (name "/PTA7") (class "Default")
      (node (ref "U2") (pin "59") (pinfunction "PTA7_59") (pintype "passive"))
    )
    (net (code "30") (name "/PTA8") (class "Default")
      (node (ref "U2") (pin "60") (pinfunction "PTA8_60") (pintype "passive"))
    )
    (net (code "31") (name "/PTA9") (class "Default")
      (node (ref "U2") (pin "61") (pinfunction "PTA9_61") (pintype "passive"))
    )
    (net (code "32") (name "/PTA10") (class "Default")
      (node (ref "U2") (pin "62") (pinfunction "PTA10_62") (pintype "passive"))
    )
    (net (code "33") (name "/PTA11") (class "Default")
      (node (ref "U1") (pin "14") (pinfunction "Q0_14") (pintype "output"))
      (node (ref "U2") (pin "63") (pinfunction "PTA11_63") (pintype "passive"))
    )
    (net (code "34") (name "/PTA12") (class "Default")
      (node (ref "R21") (pin "1") (pinfunction "1_1") (pintype "passive"))
      (node (ref "U2") (pin "64") (pinfunction "PTA12_64") (pintype "passive"))
    )
    (net (code "35") (name "/PTA13") (class "Default")
      (node (ref "U2") (pin "65") (pinfunction "PTA13_65") (pintype "passive"))
    )
    (net (code "36") (name "/PTA14") (class "Default")
      (node (ref "NRF1") (pin "5") (pinfunction "5_5") (pintype "passive"))
      (node (ref "U2") (pin "66") (pinfunction "PTA14_66") (pintype "passive"))
    )
    (net (code "37") (name "/PTA15") (class "Default")
      (node (ref "NRF1") (pin "4") (pinfunction "4_4") (pintype "passive"))
      (node (ref "U2") (pin "67") (pinfunction "PTA15_67") (pintype "passive"))
    )
    (net (code "38") (name "/PTA16") (class "Default")
      (node (ref "NRF1") (pin "3") (pinfunction "3_3") (pintype "passive"))
      (node (ref "U2") (pin "68") (pinfunction "PTA16_68") (pintype "passive"))
    )
    (net (code "39") (name "/PTA17") (class "Default")
      (node (ref "NRF1") (pin "2") (pinfunction "2_2") (pintype "passive"))
      (node (ref "U2") (pin "69") (pinfunction "PTA17_69") (pintype "passive"))
    )
    (net (code "40") (name "/PTA19") (class "Default")
      (node (ref "U2") (pin "73") (pinfunction "PTA19_73") (pintype "passive"))
    )
    (net (code "41") (name "/PTA24") (class "Default")
      (node (ref "U2") (pin "75") (pinfunction "PTA24_75") (pintype "passive"))
    )
    (net (code "42") (name "/PTA25") (class "Default")
      (node (ref "CAMER1") (pin "19") (pinfunction "SDA_19") (pintype "passive"))
      (node (ref "U2") (pin "76") (pinfunction "PTA25_76") (pintype "passive"))
    )
    (net (code "43") (name "/PTA26") (class "Default")
      (node (ref "CAMER1") (pin "17") (pinfunction "SCL_17") (pintype "passive"))
      (node (ref "U2") (pin "77") (pinfunction "PTA26_77") (pintype "passive"))
    )
    (net (code "44") (name "/PTA27") (class "Default")
      (node (ref "CAMER1") (pin "8") (pinfunction "PCL_8") (pintype "passive"))
      (node (ref "U2") (pin "78") (pinfunction "PTA27_78") (pintype "passive"))
    )
    (net (code "45") (name "/PTA28") (class "Default")
      (node (ref "CAMER1") (pin "18") (pinfunction "HRF_18") (pintype "passive"))
      (node (ref "U2") (pin "79") (pinfunction "PTA28_79") (pintype "passive"))
    )
    (net (code "46") (name "/PTA29") (class "Default")
      (node (ref "CAMER1") (pin "12") (pinfunction "V5Y_12") (pintype "passive"))
      (node (ref "U2") (pin "80") (pinfunction "PTA29_80") (pintype "passive"))
    )
    (net (code "47") (name "/PTB0") (class "Default")
      (node (ref "CAMER1") (pin "1") (pinfunction "D0_1") (pintype "passive"))
      (node (ref "U2") (pin "81") (pinfunction "PTB0_81") (pintype "passive"))
    )
    (net (code "48") (name "/PTB1") (class "Default")
      (node (ref "CAMER1") (pin "3") (pinfunction "D1_3") (pintype "passive"))
      (node (ref "U2") (pin "82") (pinfunction "PTB1_82") (pintype "passive"))
    )
    (net (code "49") (name "/PTB2") (class "Default")
      (node (ref "CAMER1") (pin "5") (pinfunction "D2_5") (pintype "passive"))
      (node (ref "U2") (pin "83") (pinfunction "PTB2_83") (pintype "passive"))
    )
    (net (code "50") (name "/PTB3") (class "Default")
      (node (ref "CAMER1") (pin "7") (pinfunction "D3_7") (pintype "passive"))
      (node (ref "U2") (pin "84") (pinfunction "PTB3_84") (pintype "passive"))
    )
    (net (code "51") (name "/PTB4") (class "Default")
      (node (ref "CAMER1") (pin "9") (pinfunction "D4_9") (pintype "passive"))
      (node (ref "U2") (pin "85") (pinfunction "PTB4_85") (pintype "passive"))
    )
    (net (code "52") (name "/PTB5") (class "Default")
      (node (ref "CAMER1") (pin "11") (pinfunction "D5_11") (pintype "passive"))
      (node (ref "U2") (pin "86") (pinfunction "PTB5_86") (pintype "passive"))
    )
    (net (code "53") (name "/PTB6") (class "Default")
      (node (ref "CAMER1") (pin "13") (pinfunction "D6_13") (pintype "passive"))
      (node (ref "U2") (pin "87") (pinfunction "PTB6_87") (pintype "passive"))
    )
    (net (code "54") (name "/PTB7") (class "Default")
      (node (ref "CAMER1") (pin "15") (pinfunction "D7_15") (pintype "passive"))
      (node (ref "U2") (pin "88") (pinfunction "PTB7_88") (pintype "passive"))
    )
    (net (code "55") (name "/PTB8") (class "Default")
      (node (ref "U2") (pin "89") (pinfunction "PTB8_89") (pintype "passive"))
    )
    (net (code "56") (name "/PTB9") (class "Default")
      (node (ref "U2") (pin "90") (pinfunction "PTB9_90") (pintype "passive"))
    )
    (net (code "57") (name "/PTB10") (class "Default")
      (node (ref "U2") (pin "91") (pinfunction "PTB10_91") (pintype "passive"))
    )
    (net (code "58") (name "/PTB11") (class "Default")
      (node (ref "U2") (pin "92") (pinfunction "PTB11_92") (pintype "passive"))
    )
    (net (code "59") (name "/PTB16") (class "Default")
      (node (ref "U2") (pin "95") (pinfunction "PTB16_95") (pintype "passive"))
    )
    (net (code "60") (name "/PTB17") (class "Default")
      (node (ref "U2") (pin "96") (pinfunction "PTB17_96") (pintype "passive"))
    )
    (net (code "61") (name "/PTB18") (class "Default")
      (node (ref "U2") (pin "97") (pinfunction "PTB18_97") (pintype "passive"))
    )
    (net (code "62") (name "/PTB19") (class "Default")
      (node (ref "U2") (pin "98") (pinfunction "PTB19_98") (pintype "passive"))
    )
    (net (code "63") (name "/PTB20") (class "Default")
      (node (ref "U2") (pin "99") (pinfunction "PTB20_99") (pintype "passive"))
    )
    (net (code "64") (name "/PTB21") (class "Default")
      (node (ref "U2") (pin "100") (pinfunction "PTB21_100") (pintype "passive"))
    )
    (net (code "65") (name "/PTB22") (class "Default")
      (node (ref "U2") (pin "101") (pinfunction "PTB22_101") (pintype "passive"))
    )
    (net (code "66") (name "/PTB23") (class "Default")
      (node (ref "U2") (pin "102") (pinfunction "PTB23_102") (pintype "passive"))
    )
    (net (code "67") (name "/PTC0") (class "Default")
      (node (ref "U2") (pin "103") (pinfunction "PTC0_103") (pintype "passive"))
    )
    (net (code "68") (name "/PTC1") (class "Default")
      (node (ref "IC3") (pin "3") (pinfunction "A1_3") (pintype "passive"))
      (node (ref "U2") (pin "104") (pinfunction "PTC1_104") (pintype "passive"))
    )
    (net (code "69") (name "/PTC2") (class "Default")
      (node (ref "IC3") (pin "5") (pinfunction "A3_5") (pintype "passive"))
      (node (ref "U2") (pin "105") (pinfunction "PTC2_105") (pintype "passive"))
    )
    (net (code "70") (name "/PTC3") (class "Default")
      (node (ref "IC3") (pin "7") (pinfunction "A5_7") (pintype "passive"))
      (node (ref "U2") (pin "106") (pinfunction "PTC3_106") (pintype "passive"))
    )
    (net (code "71") (name "/PTC4") (class "Default")
      (node (ref "IC3") (pin "9") (pinfunction "A7_9") (pintype "passive"))
      (node (ref "U2") (pin "109") (pinfunction "PTC4_109") (pintype "passive"))
    )
    (net (code "72") (name "/PTC5") (class "Default")
      (node (ref "U2") (pin "110") (pinfunction "PTC5_110") (pintype "passive"))
    )
    (net (code "73") (name "/PTC6") (class "Default")
      (node (ref "U2") (pin "111") (pinfunction "PTC6_111") (pintype "passive"))
    )
    (net (code "74") (name "/PTC7") (class "Default")
      (node (ref "U2") (pin "112") (pinfunction "PTC7_112") (pintype "passive"))
    )
    (net (code "75") (name "/PTC8") (class "Default")
      (node (ref "U2") (pin "113") (pinfunction "PTC8_113") (pintype "passive"))
    )
    (net (code "76") (name "/PTC9") (class "Default")
      (node (ref "U2") (pin "114") (pinfunction "PTC9_114") (pintype "passive"))
    )
    (net (code "77") (name "/PTC10") (class "Default")
      (node (ref "U2") (pin "115") (pinfunction "PTC10_115") (pintype "passive"))
    )
    (net (code "78") (name "/PTC11") (class "Default")
      (node (ref "U2") (pin "116") (pinfunction "PTC11_116") (pintype "passive"))
    )
    (net (code "79") (name "/PTC12") (class "Default")
      (node (ref "U2") (pin "117") (pinfunction "PTC12_117") (pintype "passive"))
    )
    (net (code "80") (name "/PTC13") (class "Default")
      (node (ref "U2") (pin "118") (pinfunction "PTC13_118") (pintype "passive"))
    )
    (net (code "81") (name "/PTC14") (class "Default")
      (node (ref "U2") (pin "119") (pinfunction "PTC14_119") (pintype "passive"))
    )
    (net (code "82") (name "/PTC15") (class "Default")
      (node (ref "U2") (pin "120") (pinfunction "PTC15_120") (pintype "passive"))
    )
    (net (code "83") (name "/PTC16") (class "Default")
      (node (ref "OLED1") (pin "6") (pinfunction "6_6") (pintype "passive"))
      (node (ref "U2") (pin "123") (pinfunction "PTC16_123") (pintype "passive"))
    )
    (net (code "84") (name "/PTC17") (class "Default")
      (node (ref "OLED1") (pin "5") (pinfunction "5_5") (pintype "passive"))
      (node (ref "U2") (pin "124") (pinfunction "PTC17_124") (pintype "passive"))
    )
    (net (code "85") (name "/PTC18") (class "Default")
      (node (ref "OLED1") (pin "4") (pinfunction "4_4") (pintype "passive"))
      (node (ref "U2") (pin "125") (pinfunction "PTC18_125") (pintype "passive"))
    )
    (net (code "86") (name "/PTC19") (class "Default")
      (node (ref "OLED1") (pin "3") (pinfunction "3_3") (pintype "passive"))
      (node (ref "U2") (pin "126") (pinfunction "PTC19_126") (pintype "passive"))
    )
    (net (code "87") (name "/PTD0") (class "Default")
      (node (ref "U2") (pin "127") (pinfunction "PTD0_127") (pintype "passive"))
    )
    (net (code "88") (name "/PTD1") (class "Default")
      (node (ref "U2") (pin "128") (pinfunction "PTD1_128") (pintype "passive"))
    )
    (net (code "89") (name "/PTD2") (class "Default")
      (node (ref "U2") (pin "129") (pinfunction "PTD2_129") (pintype "passive"))
    )
    (net (code "90") (name "/PTD3") (class "Default")
      (node (ref "U2") (pin "130") (pinfunction "PTD3_130") (pintype "passive"))
    )
    (net (code "91") (name "/PTD4") (class "Default")
      (node (ref "U1") (pin "2") (pinfunction "CLK_2") (pintype "input"))
      (node (ref "U2") (pin "131") (pinfunction "PTD4_131") (pintype "passive"))
    )
    (net (code "92") (name "/PTD5") (class "Default")
      (node (ref "*1") (pin "2") (pintype "passive"))
      (node (ref "U2") (pin "132") (pinfunction "PTD5_132") (pintype "passive"))
    )
    (net (code "93") (name "/PTD6") (class "Default")
      (node (ref "Key_4") (pin "1") (pinfunction "1_1") (pintype "passive"))
      (node (ref "U2") (pin "133") (pinfunction "PTD6_133") (pintype "passive"))
    )
    (net (code "94") (name "/PTD7") (class "Default")
      (node (ref "Key_3") (pin "1") (pinfunction "1_1") (pintype "passive"))
      (node (ref "U2") (pin "136") (pinfunction "PTD7_136") (pintype "passive"))
    )
    (net (code "95") (name "/PTD8") (class "Default")
      (node (ref "Key_2") (pin "1") (pinfunction "1_1") (pintype "passive"))
      (node (ref "U2") (pin "137") (pinfunction "PTD8_137") (pintype "passive"))
    )
    (net (code "96") (name "/PTD9") (class "Default")
      (node (ref "Key_1") (pin "1") (pinfunction "1_1") (pintype "passive"))
      (node (ref "U2") (pin "138") (pinfunction "PTD9_138") (pintype "passive"))
    )
    (net (code "97") (name "/PTD10") (class "Default")
      (node (ref "MUSW1") (pin "3") (pintype "passive"))
      (node (ref "U2") (pin "139") (pinfunction "PTD10_139") (pintype "passive"))
    )
    (net (code "98") (name "/PTD11") (class "Default")
      (node (ref "MUSW1") (pin "2") (pintype "passive"))
      (node (ref "U2") (pin "140") (pinfunction "PTD11_140") (pintype "passive"))
    )
    (net (code "99") (name "/PTD12") (class "Default")
      (node (ref "MUSW1") (pin "1") (pintype "passive"))
      (node (ref "U2") (pin "141") (pinfunction "PTD12_141") (pintype "passive"))
    )
    (net (code "100") (name "/PTD13") (class "Default")
      (node (ref "MUSW1") (pin "6") (pintype "passive"))
      (node (ref "U2") (pin "142") (pinfunction "PTD13_142") (pintype "passive"))
    )
    (net (code "101") (name "/PTD14") (class "Default")
      (node (ref "MUSW1") (pin "5") (pintype "passive"))
      (node (ref "U2") (pin "143") (pinfunction "PTD14_143") (pintype "passive"))
    )
    (net (code "102") (name "/PTE7") (class "Default")
      (node (ref "U2") (pin "10") (pinfunction "PTE7_10") (pintype "passive"))
      (node (ref "expand1") (pin "1") (pinfunction "1_1") (pintype "passive"))
    )
    (net (code "103") (name "/PTE8") (class "Default")
      (node (ref "U2") (pin "11") (pinfunction "PTE8_11") (pintype "passive"))
      (node (ref "expand1") (pin "2") (pinfunction "2_2") (pintype "passive"))
    )
    (net (code "104") (name "/PTE9") (class "Default")
      (node (ref "CCD1") (pin "1") (pinfunction "1_1") (pintype "passive"))
      (node (ref "U2") (pin "12") (pinfunction "PTE9_12") (pintype "passive"))
    )
    (net (code "105") (name "/PTE10") (class "Default")
      (node (ref "CCD1") (pin "2") (pinfunction "2_2") (pintype "passive"))
      (node (ref "U2") (pin "13") (pinfunction "PTE10_13") (pintype "passive"))
    )
    (net (code "106") (name "/PTE11") (class "Default")
      (node (ref "U2") (pin "14") (pinfunction "PTE11_14") (pintype "passive"))
      (node (ref "expand1") (pin "3") (pinfunction "3_3") (pintype "passive"))
    )
    (net (code "107") (name "/PTE12") (class "Default")
      (node (ref "U2") (pin "15") (pinfunction "PTE12_15") (pintype "passive"))
      (node (ref "expand1") (pin "4") (pinfunction "4_4") (pintype "passive"))
    )
    (net (code "108") (name "/PTE26") (class "Default")
      (node (ref "U2") (pin "47") (pinfunction "PTE26_47") (pintype "passive"))
    )
    (net (code "109") (name "/PTE27") (class "Default")
      (node (ref "NRF1") (pin "1") (pinfunction "1_1") (pintype "passive"))
      (node (ref "U2") (pin "48") (pinfunction "PTE27_48") (pintype "passive"))
    )
    (net (code "110") (name "/PTE28") (class "Default")
      (node (ref "NRF1") (pin "6") (pinfunction "6_6") (pintype "passive"))
      (node (ref "U2") (pin "49") (pinfunction "PTE28_49") (pintype "passive"))
    )
    (net (code "111") (name "/PWM1") (class "Default")
      (node (ref "IC3") (pin "17") (pinfunction "B1_17") (pintype "passive"))
      (node (ref "IR1") (pin "2") (pinfunction "IN_2") (pintype "passive"))
    )
    (net (code "112") (name "/PWM2") (class "Default")
      (node (ref "IC3") (pin "15") (pinfunction "B3_15") (pintype "passive"))
      (node (ref "IR2") (pin "2") (pinfunction "IN_2") (pintype "passive"))
    )
    (net (code "113") (name "/PWM3") (class "Default")
      (node (ref "IC3") (pin "13") (pinfunction "B5_13") (pintype "passive"))
      (node (ref "IR3") (pin "2") (pinfunction "IN_2") (pintype "passive"))
    )
    (net (code "114") (name "/PWM4") (class "Default")
      (node (ref "IC3") (pin "11") (pinfunction "B7_11") (pintype "passive"))
      (node (ref "IR4") (pin "2") (pinfunction "IN_2") (pintype "passive"))
    )
    (net (code "115") (name "/PWM_STEER") (class "Default")
      (node (ref "*1") (pin "4") (pintype "passive"))
      (node (ref "R4") (pin "1") (pinfunction "1_1") (pintype "passive"))
      (node (ref "STEER1") (pin "1") (pinfunction "Server_1") (pintype "passive"))
    )
    (net (code "116") (name "/RESET") (class "Default")
      (node (ref "C26") (pin "2") (pinfunction "2_2") (pintype "passive"))
      (node (ref "JTAG1") (pin "10") (pinfunction "10_10") (pintype "passive"))
      (node (ref "R39") (pin "1") (pinfunction "1_1") (pintype "passive"))
      (node (ref "RST1") (pin "1") (pinfunction "1_1") (pintype "passive"))
      (node (ref "U2") (pin "74") (pinfunction "RESET_b_74") (pintype "passive"))
    )
    (net (code "117") (name "/RX") (class "Default")
      (node (ref "U2") (pin "46") (pinfunction "PTE25_46") (pintype "passive"))
      (node (ref "ZIGBEE1") (pin "2") (pinfunction "2_2") (pintype "passive"))
    )
    (net (code "118") (name "/SD") (class "Default")
      (node (ref "IC3") (pin "18") (pinfunction "B0_18") (pintype "passive"))
      (node (ref "IR1") (pin "3") (pinfunction "~{SD}_3") (pintype "passive"))
      (node (ref "IR2") (pin "3") (pinfunction "~{SD}_3") (pintype "passive"))
      (node (ref "IR3") (pin "3") (pinfunction "~{SD}_3") (pintype "passive"))
      (node (ref "IR4") (pin "3") (pinfunction "~{SD}_3") (pintype "passive"))
    )
    (net (code "119") (name "/TCLK") (class "Default")
      (node (ref "JTAG1") (pin "4") (pinfunction "4_4") (pintype "passive"))
      (node (ref "U2") (pin "50") (pinfunction "PTA0_50") (pintype "passive"))
    )
    (net (code "120") (name "/TDI") (class "Default")
      (node (ref "JTAG1") (pin "8") (pinfunction "8_8") (pintype "passive"))
      (node (ref "U2") (pin "51") (pinfunction "PTA1_51") (pintype "passive"))
    )
    (net (code "121") (name "/TDO") (class "Default")
      (node (ref "JTAG1") (pin "6") (pinfunction "6_6") (pintype "passive"))
      (node (ref "U2") (pin "52") (pinfunction "PTA2_52") (pintype "passive"))
    )
    (net (code "122") (name "/TMS") (class "Default")
      (node (ref "JTAG1") (pin "2") (pinfunction "2_2") (pintype "passive"))
      (node (ref "U2") (pin "53") (pinfunction "PTA3_53") (pintype "passive"))
    )
    (net (code "123") (name "/TX") (class "Default")
      (node (ref "U2") (pin "45") (pinfunction "PTE24_45") (pintype "passive"))
      (node (ref "ZIGBEE1") (pin "3") (pinfunction "3_3") (pintype "passive"))
    )
    (net (code "124") (name "/VBAT") (class "Default")
      (node (ref "D3") (pin "2") (pinfunction "K_2") (pintype "passive"))
      (node (ref "U2") (pin "42") (pinfunction "VBAT_42") (pintype "passive"))
    )
    (net (code "125") (name "/VDDA") (class "Default")
      (node (ref "C24") (pin "2") (pinfunction "2_2") (pintype "passive"))
      (node (ref "C25") (pin "2") (pinfunction "2_2") (pintype "passive"))
      (node (ref "L2") (pin "2") (pinfunction "2_2") (pintype "passive"))
      (node (ref "L4") (pin "1") (pinfunction "1_1") (pintype "passive"))
      (node (ref "U2") (pin "31") (pinfunction "VDDA_31") (pintype "passive"))
    )
    (net (code "126") (name "/VRH") (class "Default")
      (node (ref "C33") (pin "1") (pinfunction "1_1") (pintype "passive"))
      (node (ref "C34") (pin "2") (pinfunction "2_2") (pintype "passive"))
      (node (ref "L4") (pin "2") (pinfunction "2_2") (pintype "passive"))
      (node (ref "U2") (pin "32") (pinfunction "VREFH_32") (pintype "passive"))
    )
    (net (code "127") (name "/VRL") (class "Default")
      (node (ref "C33") (pin "2") (pinfunction "2_2") (pintype "passive"))
      (node (ref "C34") (pin "1") (pinfunction "1_1") (pintype "passive"))
      (node (ref "L5") (pin "2") (pinfunction "2_2") (pintype "passive"))
      (node (ref "U2") (pin "33") (pinfunction "VREFL_33") (pintype "passive"))
    )
    (net (code "128") (name "/VSSA") (class "Default")
      (node (ref "C24") (pin "1") (pinfunction "1_1") (pintype "passive"))
      (node (ref "C25") (pin "1") (pinfunction "1_1") (pintype "passive"))
      (node (ref "L3") (pin "2") (pinfunction "2_2") (pintype "passive"))
      (node (ref "L5") (pin "1") (pinfunction "1_1") (pintype "passive"))
      (node (ref "U2") (pin "34") (pinfunction "VSSA_34") (pintype "passive"))
    )
    (net (code "129") (name "/XTAL32") (class "Default")
      (node (ref "C15") (pin "1") (pinfunction "1_1") (pintype "passive"))
      (node (ref "R14") (pin "1") (pinfunction "1_1") (pintype "passive"))
      (node (ref "U2") (pin "40") (pinfunction "XTAL32_40") (pintype "passive"))
      (node (ref "X1") (pin "1") (pinfunction "1_1") (pintype "passive"))
    )
    (net (code "130") (name "Battery") (class "Default")
      (node (ref "AM1") (pin "3") (pinfunction "I_3") (pintype "passive"))
      (node (ref "AM2") (pin "3") (pinfunction "I_3") (pintype "passive"))
      (node (ref "AM3") (pin "3") (pinfunction "I_3") (pintype "passive"))
      (node (ref "C7") (pin "1") (pinfunction "1_1") (pintype "passive"))
      (node (ref "C8") (pin "1") (pinfunction "1_1") (pintype "passive"))
      (node (ref "CA1") (pin "1") (pinfunction "1_1") (pintype "passive"))
      (node (ref "CA2") (pin "1") (pinfunction "1_1") (pintype "passive"))
      (node (ref "CA3") (pin "1") (pinfunction "1_1") (pintype "passive"))
      (node (ref "CA4") (pin "1") (pinfunction "1_1") (pintype "passive"))
      (node (ref "D2") (pin "1") (pinfunction "A_1") (pintype "passive"))
      (node (ref "Q10") (pin "1") (pinfunction "D_1") (pintype "passive"))
      (node (ref "Q4") (pin "1") (pinfunction "D_1") (pintype "passive"))
      (node (ref "Q5") (pin "1") (pinfunction "D_1") (pintype "passive"))
      (node (ref "Q9") (pin "1") (pinfunction "D_1") (pintype "passive"))
      (node (ref "SW_ENG1") (pin "2") (pintype "passive"))
    )
    (net (code "131") (name "DGND") (class "Default")
      (node (ref "*1") (pin "3") (pintype "passive"))
      (node (ref "1") (pin "1") (pinfunction "1_1") (pintype "passive"))
      (node (ref "2") (pin "1") (pinfunction "1_1") (pintype "passive"))
      (node (ref "3") (pin "1") (pinfunction "1_1") (pintype "passive"))
      (node (ref "AM1") (pin "1") (pinfunction "G_1") (pintype "passive"))
      (node (ref "AM2") (pin "1") (pinfunction "G_1") (pintype "passive"))
      (node (ref "AM3") (pin "1") (pinfunction "G_1") (pintype "passive"))
      (node (ref "BM1") (pin "1") (pinfunction "1_1") (pintype "passive"))
      (node (ref "BM2") (pin "1") (pinfunction "1_1") (pintype "passive"))
      (node (ref "C1") (pin "2") (pinfunction "2_2") (pintype "passive"))
      (node (ref "C10") (pin "2") (pinfunction "2_2") (pintype "passive"))
      (node (ref "C11") (pin "1") (pinfunction "1_1") (pintype "passive"))
      (node (ref "C12") (pin "2") (pinfunction "2_2") (pintype "passive"))
      (node (ref "C13") (pin "1") (pinfunction "1_1") (pintype "passive"))
      (node (ref "C14") (pin "2") (pinfunction "2_2") (pintype "passive"))
      (node (ref "C15") (pin "2") (pinfunction "2_2") (pintype "passive"))
      (node (ref "C16") (pin "2") (pinfunction "2_2") (pintype "passive"))
      (node (ref "C2") (pin "1") (pinfunction "1_1") (pintype "passive"))
      (node (ref "C23") (pin "2") (pinfunction "2_2") (pintype "passive"))
      (node (ref "C26") (pin "1") (pinfunction "1_1") (pintype "passive"))
      (node (ref "C27") (pin "1") (pinfunction "1_1") (pintype "passive"))
      (node (ref "C28") (pin "2") (pinfunction "2_2") (pintype "passive"))
      (node (ref "C29") (pin "1") (pinfunction "1_1") (pintype "passive"))
      (node (ref "C3") (pin "1") (pinfunction "1_1") (pintype "passive"))
      (node (ref "C30") (pin "2") (pinfunction "2_2") (pintype "passive"))
      (node (ref "C31") (pin "2") (pinfunction "2_2") (pintype "passive"))
      (node (ref "C32") (pin "2") (pinfunction "2_2") (pintype "passive"))
      (node (ref "C35") (pin "1") (pinfunction "1_1") (pintype "passive"))
      (node (ref "C36") (pin "1") (pinfunction "1_1") (pintype "passive"))
      (node (ref "C37") (pin "2") (pinfunction "2_2") (pintype "passive"))
      (node (ref "C4") (pin "2") (pinfunction "2_2") (pintype "passive"))
      (node (ref "C5") (pin "2") (pinfunction "2_2") (pintype "passive"))
      (node (ref "C6") (pin "2") (pinfunction "2_2") (pintype "passive"))
      (node (ref "C7") (pin "2") (pinfunction "2_2") (pintype "passive"))
      (node (ref "C8") (pin "2") (pinfunction "2_2") (pintype "passive"))
      (node (ref "C9") (pin "2") (pinfunction "2_2") (pintype "passive"))
      (node (ref "CA1") (pin "2") (pinfunction "2_2") (pintype "passive"))
      (node (ref "CA2") (pin "2") (pinfunction "2_2") (pintype "passive"))
      (node (ref "CA3") (pin "2") (pinfunction "2_2") (pintype "passive"))
      (node (ref "CA4") (pin "2") (pinfunction "2_2") (pintype "passive"))
      (node (ref "CAMER1") (pin "20") (pinfunction "GND_20") (pintype "passive"))
      (node (ref "CCD1") (pin "5") (pinfunction "5_5") (pintype "passive"))
      (node (ref "CIN1") (pin "2") (pinfunction "2_2") (pintype "passive"))
      (node (ref "CIN2") (pin "2") (pinfunction "2_2") (pintype "passive"))
      (node (ref "CO1") (pin "2") (pinfunction "2_2") (pintype "passive"))
      (node (ref "CO2") (pin "2") (pinfunction "2_2") (pintype "passive"))
      (node (ref "CO3") (pin "2") (pinfunction "2_2") (pintype "passive"))
      (node (ref "CON1") (pin "1") (pinfunction "1_1") (pintype "passive"))
      (node (ref "D11") (pin "1") (pinfunction "A_1") (pintype "passive"))
      (node (ref "D12") (pin "1") (pinfunction "A_1") (pintype "passive"))
      (node (ref "D18") (pin "1") (pinfunction "A_1") (pintype "passive"))
      (node (ref "D19") (pin "1") (pinfunction "A_1") (pintype "passive"))
      (node (ref "D4") (pin "1") (pinfunction "A_1") (pintype "passive"))
      (node (ref "D5") (pin "1") (pinfunction "A_1") (pintype "passive"))
      (node (ref "D6") (pin "2") (pinfunction "K_2") (pintype "passive"))
      (node (ref "IC1") (pin "1") (pinfunction "GND_1") (pintype "passive"))
      (node (ref "IC1") (pin "3") (pinfunction "0V_3") (pintype "passive"))
      (node (ref "IC2") (pin "4") (pinfunction "GND_4") (pintype "passive"))
      (node (ref "IC3") (pin "10") (pinfunction "GND_10") (pintype "passive"))
      (node (ref "IC3") (pin "19") (pinfunction "~{OE}_19") (pintype "passive"))
      (node (ref "IR1") (pin "4") (pinfunction "GND_4") (pintype "power_in"))
      (node (ref "IR2") (pin "4") (pinfunction "GND_4") (pintype "power_in"))
      (node (ref "IR3") (pin "4") (pinfunction "GND_4") (pintype "power_in"))
      (node (ref "IR4") (pin "4") (pinfunction "GND_4") (pintype "power_in"))
      (node (ref "JTAG1") (pin "3") (pinfunction "3_3") (pintype "passive"))
      (node (ref "JTAG1") (pin "5") (pinfunction "5_5") (pintype "passive"))
      (node (ref "Key_1") (pin "2") (pinfunction "2_2") (pintype "passive"))
      (node (ref "Key_2") (pin "2") (pinfunction "2_2") (pintype "passive"))
      (node (ref "Key_3") (pin "2") (pinfunction "2_2") (pintype "passive"))
      (node (ref "Key_4") (pin "2") (pinfunction "2_2") (pintype "passive"))
      (node (ref "L3") (pin "1") (pinfunction "1_1") (pintype "passive"))
      (node (ref "MIC_SD1") (pin "6") (pinfunction "6_6") (pintype "passive"))
      (node (ref "MIC_SD1") (pin "9") (pinfunction "9_9") (pintype "passive"))
      (node (ref "MUSW1") (pin "4") (pintype "passive"))
      (node (ref "ManD1") (pin "2") (pinfunction "2_2") (pintype "passive"))
      (node (ref "NRF1") (pin "8") (pinfunction "8_8") (pintype "passive"))
      (node (ref "OLED1") (pin "1") (pinfunction "1_1") (pintype "passive"))
      (node (ref "Q11") (pin "3") (pinfunction "S_3") (pintype "passive"))
      (node (ref "Q12") (pin "3") (pinfunction "S_3") (pintype "passive"))
      (node (ref "Q3") (pin "3") (pinfunction "E_3") (pintype "passive"))
      (node (ref "Q6") (pin "3") (pinfunction "S_3") (pintype "passive"))
      (node (ref "Q7") (pin "3") (pinfunction "S_3") (pintype "passive"))
      (node (ref "Q8") (pin "3") (pinfunction "E_3") (pintype "passive"))
      (node (ref "R1") (pin "1") (pinfunction "1_1") (pintype "passive"))
      (node (ref "R19") (pin "2") (pinfunction "2_2") (pintype "passive"))
      (node (ref "R2") (pin "2") (pinfunction "2_2") (pintype "passive"))
      (node (ref "R20") (pin "2") (pinfunction "2_2") (pintype "passive"))
      (node (ref "R28") (pin "1") (pinfunction "1_1") (pintype "passive"))
      (node (ref "R28") (pin "2") (pinfunction "2_2") (pintype "passive"))
      (node (ref "R29") (pin "2") (pinfunction "2_2") (pintype "passive"))
      (node (ref "R30") (pin "2") (pinfunction "2_2") (pintype "passive"))
      (node (ref "R31") (pin "1") (pinfunction "1_1") (pintype "passive"))
      (node (ref "R31") (pin "2") (pinfunction "2_2") (pintype "passive"))
      (node (ref "R38") (pin "1") (pinfunction "1_1") (pintype "passive"))
      (node (ref "R38") (pin "2") (pinfunction "2_2") (pintype "passive"))
      (node (ref "R40") (pin "1") (pinfunction "1_1") (pintype "passive"))
      (node (ref "R40") (pin "2") (pinfunction "2_2") (pintype "passive"))
      (node (ref "R7") (pin "2") (pinfunction "2_2") (pintype "passive"))
      (node (ref "R8") (pin "1") (pinfunction "1_1") (pintype "passive"))
      (node (ref "R9") (pin "2") (pinfunction "2_2") (pintype "passive"))
      (node (ref "RST1") (pin "2") (pinfunction "2_2") (pintype "passive"))
      (node (ref "STEER1") (pin "3") (pinfunction "GND_3") (pintype "power_in"))
      (node (ref "U1") (pin "3") (pinfunction "P0_3") (pintype "input"))
      (node (ref "U1") (pin "4") (pinfunction "P1_4") (pintype "input"))
      (node (ref "U1") (pin "5") (pinfunction "P2_5") (pintype "input"))
      (node (ref "U1") (pin "6") (pinfunction "P3_6") (pintype "input"))
      (node (ref "U1") (pin "8") (pinfunction "GND_8") (pintype "power_in"))
      (node (ref "U2") (pin "107") (pinfunction "VSS_107") (pintype "passive"))
      (node (ref "U2") (pin "121") (pinfunction "VSS_121") (pintype "passive"))
      (node (ref "U2") (pin "134") (pinfunction "VSS_134") (pintype "passive"))
      (node (ref "U2") (pin "17") (pinfunction "VSS_17") (pintype "passive"))
      (node (ref "U2") (pin "18") (pinfunction "VSS_18") (pintype "passive"))
      (node (ref "U2") (pin "19") (pinfunction "USB0_DP_19") (pintype "passive"))
      (node (ref "U2") (pin "20") (pinfunction "USB0_DM_20") (pintype "passive"))
      (node (ref "U2") (pin "21") (pinfunction "VOUT33_21") (pintype "passive"))
      (node (ref "U2") (pin "22") (pinfunction "VREGIN_22") (pintype "passive"))
      (node (ref "U2") (pin "44") (pinfunction "VSS_44") (pintype "passive"))
      (node (ref "U2") (pin "57") (pinfunction "VSS_57") (pintype "passive"))
      (node (ref "U2") (pin "6") (pinfunction "VSS_6") (pintype "passive"))
      (node (ref "U2") (pin "71") (pinfunction "VSS_71") (pintype "passive"))
      (node (ref "U2") (pin "93") (pinfunction "VSS_93") (pintype "passive"))
      (node (ref "Y1") (pin "1") (pinfunction "1_1") (pintype "passive"))
      (node (ref "ZIGBEE1") (pin "4") (pinfunction "4_4") (pintype "passive"))
    )
    (net (code "132") (name "MPU_3V3") (class "Default")
      (node (ref "C23") (pin "1") (pinfunction "1_1") (pintype "passive"))
      (node (ref "C27") (pin "2") (pinfunction "2_2") (pintype "passive"))
      (node (ref "C28") (pin "1") (pinfunction "1_1") (pintype "passive"))
      (node (ref "C29") (pin "2") (pinfunction "2_2") (pintype "passive"))
      (node (ref "C30") (pin "1") (pinfunction "1_1") (pintype "passive"))
      (node (ref "C31") (pin "1") (pinfunction "1_1") (pintype "passive"))
      (node (ref "C32") (pin "1") (pinfunction "1_1") (pintype "passive"))
      (node (ref "C35") (pin "2") (pinfunction "2_2") (pintype "passive"))
      (node (ref "C36") (pin "2") (pinfunction "2_2") (pintype "passive"))
      (node (ref "C37") (pin "1") (pinfunction "1_1") (pintype "passive"))
      (node (ref "D13") (pin "2") (pinfunction "K_2") (pintype "passive"))
      (node (ref "D3") (pin "1") (pinfunction "A_1") (pintype "passive"))
      (node (ref "D4") (pin "2") (pinfunction "K_2") (pintype "passive"))
      (node (ref "D5") (pin "2") (pinfunction "K_2") (pintype "passive"))
      (node (ref "F1") (pin "2") (pinfunction "2_2") (pintype "passive"))
      (node (ref "JTAG1") (pin "1") (pinfunction "1_1") (pintype "passive"))
      (node (ref "L2") (pin "1") (pinfunction "1_1") (pintype "passive"))
      (node (ref "MIC_SD1") (pin "4") (pinfunction "4_4") (pintype "passive"))
      (node (ref "OLED1") (pin "2") (pinfunction "2_2") (pintype "passive"))
      (node (ref "R11") (pin "1") (pinfunction "1_1") (pintype "passive"))
      (node (ref "R32") (pin "1") (pinfunction "1_1") (pintype "passive"))
      (node (ref "R33") (pin "1") (pinfunction "1_1") (pintype "passive"))
      (node (ref "R34") (pin "1") (pinfunction "1_1") (pintype "passive"))
      (node (ref "R35") (pin "1") (pinfunction "1_1") (pintype "passive"))
      (node (ref "R36") (pin "1") (pinfunction "1_1") (pintype "passive"))
      (node (ref "R37") (pin "1") (pinfunction "1_1") (pintype "passive"))
      (node (ref "R39") (pin "2") (pinfunction "2_2") (pintype "passive"))
      (node (ref "TMB1") (pin "1") (pinfunction "A_1") (pintype "passive"))
      (node (ref "U2") (pin "108") (pinfunction "VDD_108") (pintype "passive"))
      (node (ref "U2") (pin "122") (pinfunction "VDD_122") (pintype "passive"))
      (node (ref "U2") (pin "135") (pinfunction "VDD_135") (pintype "passive"))
      (node (ref "U2") (pin "16") (pinfunction "VDD_16") (pintype "passive"))
      (node (ref "U2") (pin "43") (pinfunction "VDD_43") (pintype "passive"))
      (node (ref "U2") (pin "5") (pinfunction "VDD_5") (pintype "passive"))
      (node (ref "U2") (pin "56") (pinfunction "VDD_56") (pintype "passive"))
      (node (ref "U2") (pin "70") (pinfunction "VDD_70") (pintype "passive"))
      (node (ref "U2") (pin "94") (pinfunction "VDD_94") (pintype "passive"))
      (node (ref "Y1") (pin "4") (pinfunction "4_4") (pintype "passive"))
    )
    (net (code "133") (name "Net-(*1-Pad1)") (class "Default")
      (node (ref "*1") (pin "1") (pintype "passive"))
      (node (ref "R3") (pin "1") (pinfunction "1_1") (pintype "passive"))
    )
    (net (code "134") (name "Net-(CON1-Pad2)") (class "Default")
      (node (ref "CON1") (pin "2") (pinfunction "2_2") (pintype "passive"))
      (node (ref "SW_ENG1") (pin "1") (pintype "passive"))
    )
    (net (code "135") (name "Net-(D1-A)") (class "Default")
      (node (ref "D1") (pin "1") (pinfunction "A_1") (pintype "passive"))
      (node (ref "IC2") (pin "1") (pinfunction "SC_1") (pintype "passive"))
      (node (ref "L1") (pin "1") (pinfunction "1_1") (pintype "passive"))
      (node (ref "Q3") (pin "1") (pinfunction "C_1") (pintype "passive"))
    )
    (net (code "136") (name "Net-(D2-K)") (class "Default")
      (node (ref "D2") (pin "2") (pinfunction "K_2") (pintype "passive"))
      (node (ref "R7") (pin "1") (pinfunction "1_1") (pintype "passive"))
    )
    (net (code "137") (name "Net-(D6-A)") (class "Default")
      (node (ref "D6") (pin "1") (pinfunction "A_1") (pintype "passive"))
      (node (ref "R11") (pin "2") (pinfunction "2_2") (pintype "passive"))
    )
    (net (code "138") (name "Net-(D7-K)") (class "Default")
      (node (ref "C18") (pin "1") (pinfunction "1_1") (pintype "passive"))
      (node (ref "D7") (pin "2") (pinfunction "K_2") (pintype "passive"))
      (node (ref "IR1") (pin "8") (pinfunction "VB_8") (pintype "passive"))
    )
    (net (code "139") (name "Net-(D8-K)") (class "Default")
      (node (ref "C19") (pin "1") (pinfunction "1_1") (pintype "passive"))
      (node (ref "D8") (pin "2") (pinfunction "K_2") (pintype "passive"))
      (node (ref "IR2") (pin "8") (pinfunction "VB_8") (pintype "passive"))
    )
    (net (code "140") (name "Net-(D9-A)") (class "Default")
      (node (ref "C17") (pin "2") (pinfunction "2_2") (pintype "passive"))
      (node (ref "C18") (pin "2") (pinfunction "2_2") (pintype "passive"))
      (node (ref "D9") (pin "1") (pinfunction "A_1") (pintype "passive"))
      (node (ref "ENG1") (pin "2") (pinfunction "2_2") (pintype "passive"))
      (node (ref "IR1") (pin "6") (pinfunction "VS_6") (pintype "passive"))
      (node (ref "Q4") (pin "3") (pinfunction "S_3") (pintype "passive"))
      (node (ref "Q6") (pin "1") (pinfunction "D_1") (pintype "passive"))
      (node (ref "R15") (pin "2") (pinfunction "2_2") (pintype "passive"))
    )
    (net (code "141") (name "Net-(D9-K)") (class "Default")
      (node (ref "D9") (pin "2") (pinfunction "K_2") (pintype "passive"))
      (node (ref "Q4") (pin "2") (pinfunction "G_2") (pintype "passive"))
      (node (ref "R12") (pin "1") (pinfunction "1_1") (pintype "passive"))
      (node (ref "R15") (pin "1") (pinfunction "1_1") (pintype "passive"))
    )
    (net (code "142") (name "Net-(D10-A)") (class "Default")
      (node (ref "C17") (pin "1") (pinfunction "1_1") (pintype "passive"))
      (node (ref "C19") (pin "2") (pinfunction "2_2") (pintype "passive"))
      (node (ref "D10") (pin "1") (pinfunction "A_1") (pintype "passive"))
      (node (ref "ENG1") (pin "1") (pinfunction "1_1") (pintype "passive"))
      (node (ref "IR2") (pin "6") (pinfunction "VS_6") (pintype "passive"))
      (node (ref "Q5") (pin "3") (pinfunction "S_3") (pintype "passive"))
      (node (ref "Q7") (pin "1") (pinfunction "D_1") (pintype "passive"))
      (node (ref "R16") (pin "2") (pinfunction "2_2") (pintype "passive"))
    )
    (net (code "143") (name "Net-(D10-K)") (class "Default")
      (node (ref "D10") (pin "2") (pinfunction "K_2") (pintype "passive"))
      (node (ref "Q5") (pin "2") (pinfunction "G_2") (pintype "passive"))
      (node (ref "R13") (pin "2") (pinfunction "2_2") (pintype "passive"))
      (node (ref "R16") (pin "1") (pinfunction "1_1") (pintype "passive"))
    )
    (net (code "144") (name "Net-(D11-K)") (class "Default")
      (node (ref "D11") (pin "2") (pinfunction "K_2") (pintype "passive"))
      (node (ref "Q6") (pin "2") (pinfunction "G_2") (pintype "passive"))
      (node (ref "R17") (pin "1") (pinfunction "1_1") (pintype "passive"))
      (node (ref "R19") (pin "1") (pinfunction "1_1") (pintype "passive"))
    )
    (net (code "145") (name "Net-(D12-K)") (class "Default")
      (node (ref "D12") (pin "2") (pinfunction "K_2") (pintype "passive"))
      (node (ref "Q7") (pin "2") (pinfunction "G_2") (pintype "passive"))
      (node (ref "R18") (pin "2") (pinfunction "2_2") (pintype "passive"))
      (node (ref "R20") (pin "1") (pinfunction "1_1") (pintype "passive"))
    )
    (net (code "146") (name "Net-(D13-A)") (class "Default")
      (node (ref "D13") (pin "1") (pinfunction "A_1") (pintype "passive"))
      (node (ref "Q8") (pin "1") (pinfunction "C_1") (pintype "passive"))
      (node (ref "TMB1") (pin "2") (pinfunction "B_2") (pintype "passive"))
    )
    (net (code "147") (name "Net-(D14-K)") (class "Default")
      (node (ref "C21") (pin "1") (pinfunction "1_1") (pintype "passive"))
      (node (ref "D14") (pin "2") (pinfunction "K_2") (pintype "passive"))
      (node (ref "IR3") (pin "8") (pinfunction "VB_8") (pintype "passive"))
    )
    (net (code "148") (name "Net-(D15-K)") (class "Default")
      (node (ref "C22") (pin "1") (pinfunction "1_1") (pintype "passive"))
      (node (ref "D15") (pin "2") (pinfunction "K_2") (pintype "passive"))
      (node (ref "IR4") (pin "8") (pinfunction "VB_8") (pintype "passive"))
    )
    (net (code "149") (name "Net-(D16-A)") (class "Default")
      (node (ref "C20") (pin "2") (pinfunction "2_2") (pintype "passive"))
      (node (ref "C21") (pin "2") (pinfunction "2_2") (pintype "passive"))
      (node (ref "D16") (pin "1") (pinfunction "A_1") (pintype "passive"))
      (node (ref "ENG2") (pin "2") (pinfunction "2_2") (pintype "passive"))
      (node (ref "IR3") (pin "6") (pinfunction "VS_6") (pintype "passive"))
      (node (ref "Q11") (pin "1") (pinfunction "D_1") (pintype "passive"))
      (node (ref "Q9") (pin "3") (pinfunction "S_3") (pintype "passive"))
      (node (ref "R25") (pin "2") (pinfunction "2_2") (pintype "passive"))
    )
    (net (code "150") (name "Net-(D16-K)") (class "Default")
      (node (ref "D16") (pin "2") (pinfunction "K_2") (pintype "passive"))
      (node (ref "Q9") (pin "2") (pinfunction "G_2") (pintype "passive"))
      (node (ref "R22") (pin "1") (pinfunction "1_1") (pintype "passive"))
      (node (ref "R25") (pin "1") (pinfunction "1_1") (pintype "passive"))
    )
    (net (code "151") (name "Net-(D17-A)") (class "Default")
      (node (ref "C20") (pin "1") (pinfunction "1_1") (pintype "passive"))
      (node (ref "C22") (pin "2") (pinfunction "2_2") (pintype "passive"))
      (node (ref "D17") (pin "1") (pinfunction "A_1") (pintype "passive"))
      (node (ref "ENG2") (pin "1") (pinfunction "1_1") (pintype "passive"))
      (node (ref "IR4") (pin "6") (pinfunction "VS_6") (pintype "passive"))
      (node (ref "Q10") (pin "3") (pinfunction "S_3") (pintype "passive"))
      (node (ref "Q12") (pin "1") (pinfunction "D_1") (pintype "passive"))
      (node (ref "R24") (pin "2") (pinfunction "2_2") (pintype "passive"))
    )
    (net (code "152") (name "Net-(D17-K)") (class "Default")
      (node (ref "D17") (pin "2") (pinfunction "K_2") (pintype "passive"))
      (node (ref "Q10") (pin "2") (pinfunction "G_2") (pintype "passive"))
      (node (ref "R23") (pin "2") (pinfunction "2_2") (pintype "passive"))
      (node (ref "R24") (pin "1") (pinfunction "1_1") (pintype "passive"))
    )
    (net (code "153") (name "Net-(D18-K)") (class "Default")
      (node (ref "D18") (pin "2") (pinfunction "K_2") (pintype "passive"))
      (node (ref "Q11") (pin "2") (pinfunction "G_2") (pintype "passive"))
      (node (ref "R26") (pin "1") (pinfunction "1_1") (pintype "passive"))
      (node (ref "R29") (pin "1") (pinfunction "1_1") (pintype "passive"))
    )
    (net (code "154") (name "Net-(D19-K)") (class "Default")
      (node (ref "D19") (pin "2") (pinfunction "K_2") (pintype "passive"))
      (node (ref "Q12") (pin "2") (pinfunction "G_2") (pintype "passive"))
      (node (ref "R27") (pin "2") (pinfunction "2_2") (pintype "passive"))
      (node (ref "R30") (pin "1") (pinfunction "1_1") (pintype "passive"))
    )
    (net (code "155") (name "Net-(IC2-DRI)") (class "Default")
      (node (ref "IC2") (pin "8") (pinfunction "DRI_8") (pintype "passive"))
      (node (ref "R6") (pin "2") (pinfunction "2_2") (pintype "passive"))
    )
    (net (code "156") (name "Net-(IC2-FB)") (class "Default")
      (node (ref "IC2") (pin "5") (pinfunction "FB_5") (pintype "passive"))
      (node (ref "R10") (pin "2") (pinfunction "1_2") (pintype "passive"))
      (node (ref "R9") (pin "1") (pinfunction "1_1") (pintype "passive"))
    )
    (net (code "157") (name "Net-(IC2-IPK)") (class "Default")
      (node (ref "IC2") (pin "7") (pinfunction "IPK_7") (pintype "passive"))
      (node (ref "L1") (pin "2") (pinfunction "2_2") (pintype "passive"))
      (node (ref "R5") (pin "1") (pinfunction "1_1") (pintype "passive"))
      (node (ref "R6") (pin "1") (pinfunction "1_1") (pintype "passive"))
    )
    (net (code "158") (name "Net-(IC2-SE)") (class "Default")
      (node (ref "IC2") (pin "2") (pinfunction "SE_2") (pintype "passive"))
      (node (ref "Q3") (pin "2") (pinfunction "B_2") (pintype "passive"))
      (node (ref "R8") (pin "2") (pinfunction "2_2") (pintype "passive"))
    )
    (net (code "159") (name "Net-(IC2-TC)") (class "Default")
      (node (ref "C12") (pin "1") (pinfunction "1_1") (pintype "passive"))
      (node (ref "IC2") (pin "3") (pinfunction "TC_3") (pintype "passive"))
    )
    (net (code "160") (name "Net-(IC2-VCC)") (class "Default")
      (node (ref "IC2") (pin "6") (pinfunction "VCC_6") (pintype "passive"))
      (node (ref "R5") (pin "2") (pinfunction "2_2") (pintype "passive"))
      (node (ref "SW_STE1") (pin "2") (pintype "passive"))
    )
    (net (code "161") (name "Net-(IR1-HO)") (class "Default")
      (node (ref "IR1") (pin "7") (pinfunction "HO_7") (pintype "passive"))
      (node (ref "R12") (pin "2") (pinfunction "2_2") (pintype "passive"))
    )
    (net (code "162") (name "Net-(IR1-LO)") (class "Default")
      (node (ref "IR1") (pin "5") (pinfunction "LO_5") (pintype "passive"))
      (node (ref "R17") (pin "2") (pinfunction "2_2") (pintype "passive"))
    )
    (net (code "163") (name "Net-(IR2-HO)") (class "Default")
      (node (ref "IR2") (pin "7") (pinfunction "HO_7") (pintype "passive"))
      (node (ref "R13") (pin "1") (pinfunction "1_1") (pintype "passive"))
    )
    (net (code "164") (name "Net-(IR2-LO)") (class "Default")
      (node (ref "IR2") (pin "5") (pinfunction "LO_5") (pintype "passive"))
      (node (ref "R18") (pin "1") (pinfunction "1_1") (pintype "passive"))
    )
    (net (code "165") (name "Net-(IR3-HO)") (class "Default")
      (node (ref "IR3") (pin "7") (pinfunction "HO_7") (pintype "passive"))
      (node (ref "R22") (pin "2") (pinfunction "2_2") (pintype "passive"))
    )
    (net (code "166") (name "Net-(IR3-LO)") (class "Default")
      (node (ref "IR3") (pin "5") (pinfunction "LO_5") (pintype "passive"))
      (node (ref "R26") (pin "2") (pinfunction "2_2") (pintype "passive"))
    )
    (net (code "167") (name "Net-(IR4-HO)") (class "Default")
      (node (ref "IR4") (pin "7") (pinfunction "HO_7") (pintype "passive"))
      (node (ref "R23") (pin "1") (pinfunction "1_1") (pintype "passive"))
    )
    (net (code "168") (name "Net-(IR4-LO)") (class "Default")
      (node (ref "IR4") (pin "5") (pinfunction "LO_5") (pintype "passive"))
      (node (ref "R27") (pin "1") (pinfunction "1_1") (pintype "passive"))
    )
    (net (code "169") (name "Net-(Q8-B)") (class "Default")
      (node (ref "Q8") (pin "2") (pinfunction "B_2") (pintype "passive"))
      (node (ref "R21") (pin "2") (pinfunction "2_2") (pintype "passive"))
    )
    (net (code "170") (name "Net-(R2-Pad1)") (class "Default")
      (node (ref "R2") (pin "1") (pinfunction "1_1") (pintype "passive"))
      (node (ref "SW_STE1") (pin "3") (pintype "passive"))
    )
    (net (code "171") (name "VCC-3.3V") (class "Default")
      (node (ref "1") (pin "3") (pinfunction "3_3") (pintype "passive"))
      (node (ref "2") (pin "3") (pinfunction "3_3") (pintype "passive"))
      (node (ref "3") (pin "3") (pinfunction "3_3") (pintype "passive"))
      (node (ref "AM2") (pin "2") (pinfunction "O_2") (pintype "passive"))
      (node (ref "BM1") (pin "2") (pinfunction "2_2") (pintype "passive"))
      (node (ref "BM2") (pin "2") (pinfunction "2_2") (pintype "passive"))
      (node (ref "C11") (pin "2") (pinfunction "2_2") (pintype "passive"))
      (node (ref "C13") (pin "2") (pinfunction "2_2") (pintype "passive"))
      (node (ref "C3") (pin "2") (pinfunction "2_2") (pintype "passive"))
      (node (ref "C4") (pin "1") (pinfunction "1_1") (pintype "passive"))
      (node (ref "C5") (pin "1") (pinfunction "1_1") (pintype "passive"))
      (node (ref "CAMER1") (pin "2") (pinfunction "3V3_2") (pintype "passive"))
      (node (ref "CCD1") (pin "4") (pinfunction "4_4") (pintype "passive"))
      (node (ref "CO2") (pin "1") (pinfunction "1_1") (pintype "passive"))
      (node (ref "IC3") (pin "1") (pinfunction "DIR_1") (pintype "passive"))
      (node (ref "NRF1") (pin "7") (pinfunction "7_7") (pintype "passive"))
      (node (ref "R3") (pin "2") (pinfunction "2_2") (pintype "passive"))
      (node (ref "ZIGBEE1") (pin "1") (pinfunction "1_1") (pintype "passive"))
    )
    (net (code "172") (name "VCC-5.5V") (class "Default")
      (node (ref "C2") (pin "2") (pinfunction "2_2") (pintype "passive"))
      (node (ref "CIN1") (pin "1") (pinfunction "1_1") (pintype "passive"))
      (node (ref "D1") (pin "2") (pinfunction "K_2") (pintype "passive"))
      (node (ref "R10") (pin "1") (pinfunction "0_1") (pintype "passive"))
      (node (ref "R4") (pin "2") (pinfunction "2_2") (pintype "passive"))
      (node (ref "STEER1") (pin "2") (pinfunction "VCC_2") (pintype "power_in"))
    )
    (net (code "173") (name "VCC-5V") (class "Default")
      (node (ref "AM1") (pin "2") (pinfunction "O_2") (pintype "passive"))
      (node (ref "C1") (pin "1") (pinfunction "1_1") (pintype "passive"))
      (node (ref "C10") (pin "1") (pinfunction "1_1") (pintype "passive"))
      (node (ref "C14") (pin "1") (pinfunction "1_1") (pintype "passive"))
      (node (ref "C6") (pin "1") (pinfunction "1_1") (pintype "passive"))
      (node (ref "CO1") (pin "1") (pinfunction "1_1") (pintype "passive"))
      (node (ref "IC1") (pin "2") (pinfunction "Vin_2") (pintype "passive"))
      (node (ref "IC3") (pin "20") (pinfunction "VCC_20") (pintype "passive"))
      (node (ref "ManD1") (pin "1") (pinfunction "1_1") (pintype "passive"))
      (node (ref "Q1") (pin "1") (pinfunction "C_1") (pintype "passive"))
      (node (ref "Q2") (pin "1") (pinfunction "C_1") (pintype "passive"))
      (node (ref "SW_STE1") (pin "1") (pintype "passive"))
      (node (ref "U1") (pin "10") (pinfunction "CET_10") (pintype "input"))
      (node (ref "U1") (pin "16") (pinfunction "VCC_16") (pintype "power_in"))
      (node (ref "U1") (pin "7") (pinfunction "CEP_7") (pintype "input"))
      (node (ref "U1") (pin "9") (pinfunction "PE_9") (pintype "input"))
    )
    (net (code "174") (name "VCC-15V") (class "Default")
      (node (ref "C9") (pin "1") (pinfunction "1_1") (pintype "passive"))
      (node (ref "D14") (pin "1") (pinfunction "A_1") (pintype "passive"))
      (node (ref "D15") (pin "1") (pinfunction "A_1") (pintype "passive"))
      (node (ref "D7") (pin "1") (pinfunction "A_1") (pintype "passive"))
      (node (ref "D8") (pin "1") (pinfunction "A_1") (pintype "passive"))
      (node (ref "IC1") (pin "4") (pinfunction "+V0_4") (pintype "passive"))
      (node (ref "IR1") (pin "1") (pinfunction "VCC_1") (pintype "power_in"))
      (node (ref "IR2") (pin "1") (pinfunction "VCC_1") (pintype "power_in"))
      (node (ref "IR3") (pin "1") (pinfunction "VCC_1") (pintype "power_in"))
      (node (ref "IR4") (pin "1") (pinfunction "VCC_1") (pintype "power_in"))
    )
    (net (code "175") (name "unconnected-(BM1-Pad4)") (class "Default")
      (node (ref "BM1") (pin "4") (pinfunction "4_4") (pintype "passive"))
    )
    (net (code "176") (name "unconnected-(BM1-Pad5)") (class "Default")
      (node (ref "BM1") (pin "5") (pinfunction "5_5") (pintype "passive+no_connect"))
    )
    (net (code "177") (name "unconnected-(BM1-Pad6)") (class "Default")
      (node (ref "BM1") (pin "6") (pinfunction "6_6") (pintype "passive+no_connect"))
    )
    (net (code "178") (name "unconnected-(BM2-Pad4)") (class "Default")
      (node (ref "BM2") (pin "4") (pinfunction "4_4") (pintype "passive"))
    )
    (net (code "179") (name "unconnected-(BM2-Pad5)") (class "Default")
      (node (ref "BM2") (pin "5") (pinfunction "5_5") (pintype "passive+no_connect"))
    )
    (net (code "180") (name "unconnected-(BM2-Pad6)") (class "Default")
      (node (ref "BM2") (pin "6") (pinfunction "6_6") (pintype "passive+no_connect"))
    )
    (net (code "181") (name "unconnected-(CAMER1-OE-Pad4)") (class "Default")
      (node (ref "CAMER1") (pin "4") (pinfunction "OE_4") (pintype "passive"))
    )
    (net (code "182") (name "unconnected-(CAMER1-RE-Pad6)") (class "Default")
      (node (ref "CAMER1") (pin "6") (pinfunction "RE_6") (pintype "passive"))
    )
    (net (code "183") (name "unconnected-(CAMER1-WEN-Pad16)") (class "Default")
      (node (ref "CAMER1") (pin "16") (pinfunction "WEN_16") (pintype "passive"))
    )
    (net (code "184") (name "unconnected-(CAMER1-WRS-Pad14)") (class "Default")
      (node (ref "CAMER1") (pin "14") (pinfunction "WRS_14") (pintype "passive"))
    )
    (net (code "185") (name "unconnected-(CAMER1-XCL-Pad10)") (class "Default")
      (node (ref "CAMER1") (pin "10") (pinfunction "XCL_10") (pintype "passive"))
    )
    (net (code "186") (name "unconnected-(IC3-A2-Pad4)") (class "Default")
      (node (ref "IC3") (pin "4") (pinfunction "A2_4") (pintype "passive"))
    )
    (net (code "187") (name "unconnected-(IC3-A4-Pad6)") (class "Default")
      (node (ref "IC3") (pin "6") (pinfunction "A4_6") (pintype "passive"))
    )
    (net (code "188") (name "unconnected-(IC3-A6-Pad8)") (class "Default")
      (node (ref "IC3") (pin "8") (pinfunction "A6_8") (pintype "passive"))
    )
    (net (code "189") (name "unconnected-(IC3-B2-Pad16)") (class "Default")
      (node (ref "IC3") (pin "16") (pinfunction "B2_16") (pintype "passive"))
    )
    (net (code "190") (name "unconnected-(IC3-B4-Pad14)") (class "Default")
      (node (ref "IC3") (pin "14") (pinfunction "B4_14") (pintype "passive"))
    )
    (net (code "191") (name "unconnected-(IC3-B6-Pad12)") (class "Default")
      (node (ref "IC3") (pin "12") (pinfunction "B6_12") (pintype "passive"))
    )
    (net (code "192") (name "unconnected-(JTAG1-Pad7)") (class "Default")
      (node (ref "JTAG1") (pin "7") (pinfunction "7_7") (pintype "passive+no_connect"))
    )
    (net (code "193") (name "unconnected-(JTAG1-Pad9)") (class "Default")
      (node (ref "JTAG1") (pin "9") (pinfunction "9_9") (pintype "passive+no_connect"))
    )
    (net (code "194") (name "unconnected-(OLED1-Pad7)") (class "Default")
      (node (ref "OLED1") (pin "7") (pinfunction "7_7") (pintype "passive+no_connect"))
    )
    (net (code "195") (name "unconnected-(R10-2-Pad3)") (class "Default")
      (node (ref "R10") (pin "3") (pinfunction "2_3") (pintype "passive"))
    )
    (net (code "196") (name "unconnected-(SW_ENG1-Pad3)") (class "Default")
      (node (ref "SW_ENG1") (pin "3") (pintype "passive"))
    )
    (net (code "197") (name "unconnected-(U1-Q1-Pad13)") (class "Default")
      (node (ref "U1") (pin "13") (pinfunction "Q1_13") (pintype "output"))
    )
    (net (code "198") (name "unconnected-(U1-Q2-Pad12)") (class "Default")
      (node (ref "U1") (pin "12") (pinfunction "Q2_12") (pintype "output"))
    )
    (net (code "199") (name "unconnected-(U1-Q3-Pad11)") (class "Default")
      (node (ref "U1") (pin "11") (pinfunction "Q3_11") (pintype "output"))
    )
    (net (code "200") (name "unconnected-(U1-TC-Pad15)") (class "Default")
      (node (ref "U1") (pin "15") (pinfunction "TC_15") (pintype "output"))
    )
    (net (code "201") (name "unconnected-(U2-PTD15-Pad144)") (class "Default")
      (node (ref "U2") (pin "144") (pinfunction "PTD15_144") (pintype "passive"))
    )
    (net (code "202") (name "unconnected-(U2-PTE6-Pad9)") (class "Default")
      (node (ref "U2") (pin "9") (pinfunction "PTE6_9") (pintype "passive"))
    )
    (net (code "203") (name "unconnected-(Y1-Pad2)") (class "Default")
      (node (ref "Y1") (pin "2") (pinfunction "2_2") (pintype "passive+no_connect"))
    )
  )
)
